# board.net
KiCad netlist of a schematic drawn in EAGLE
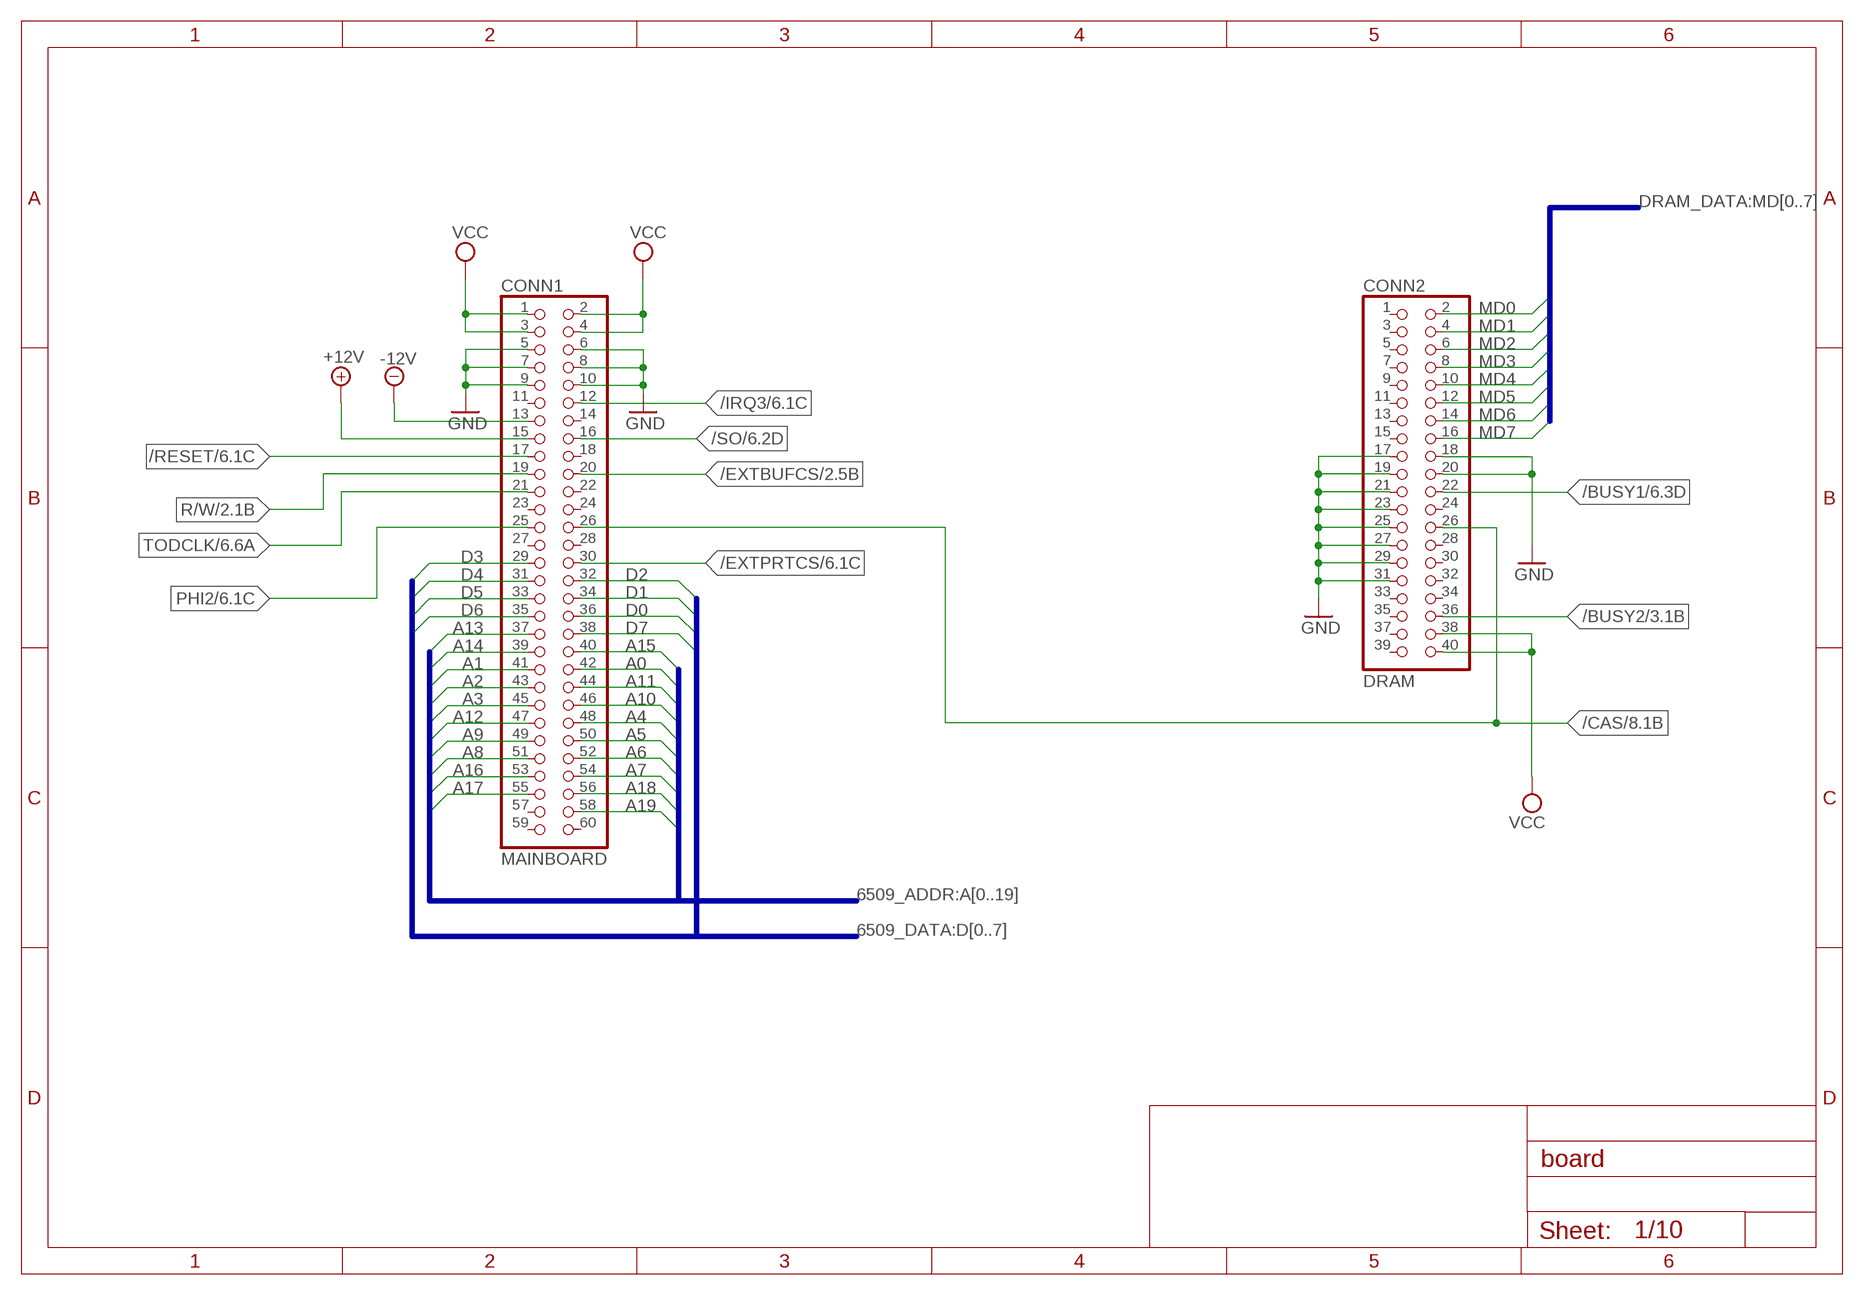
[diagram p0: schematic, sheet 1]
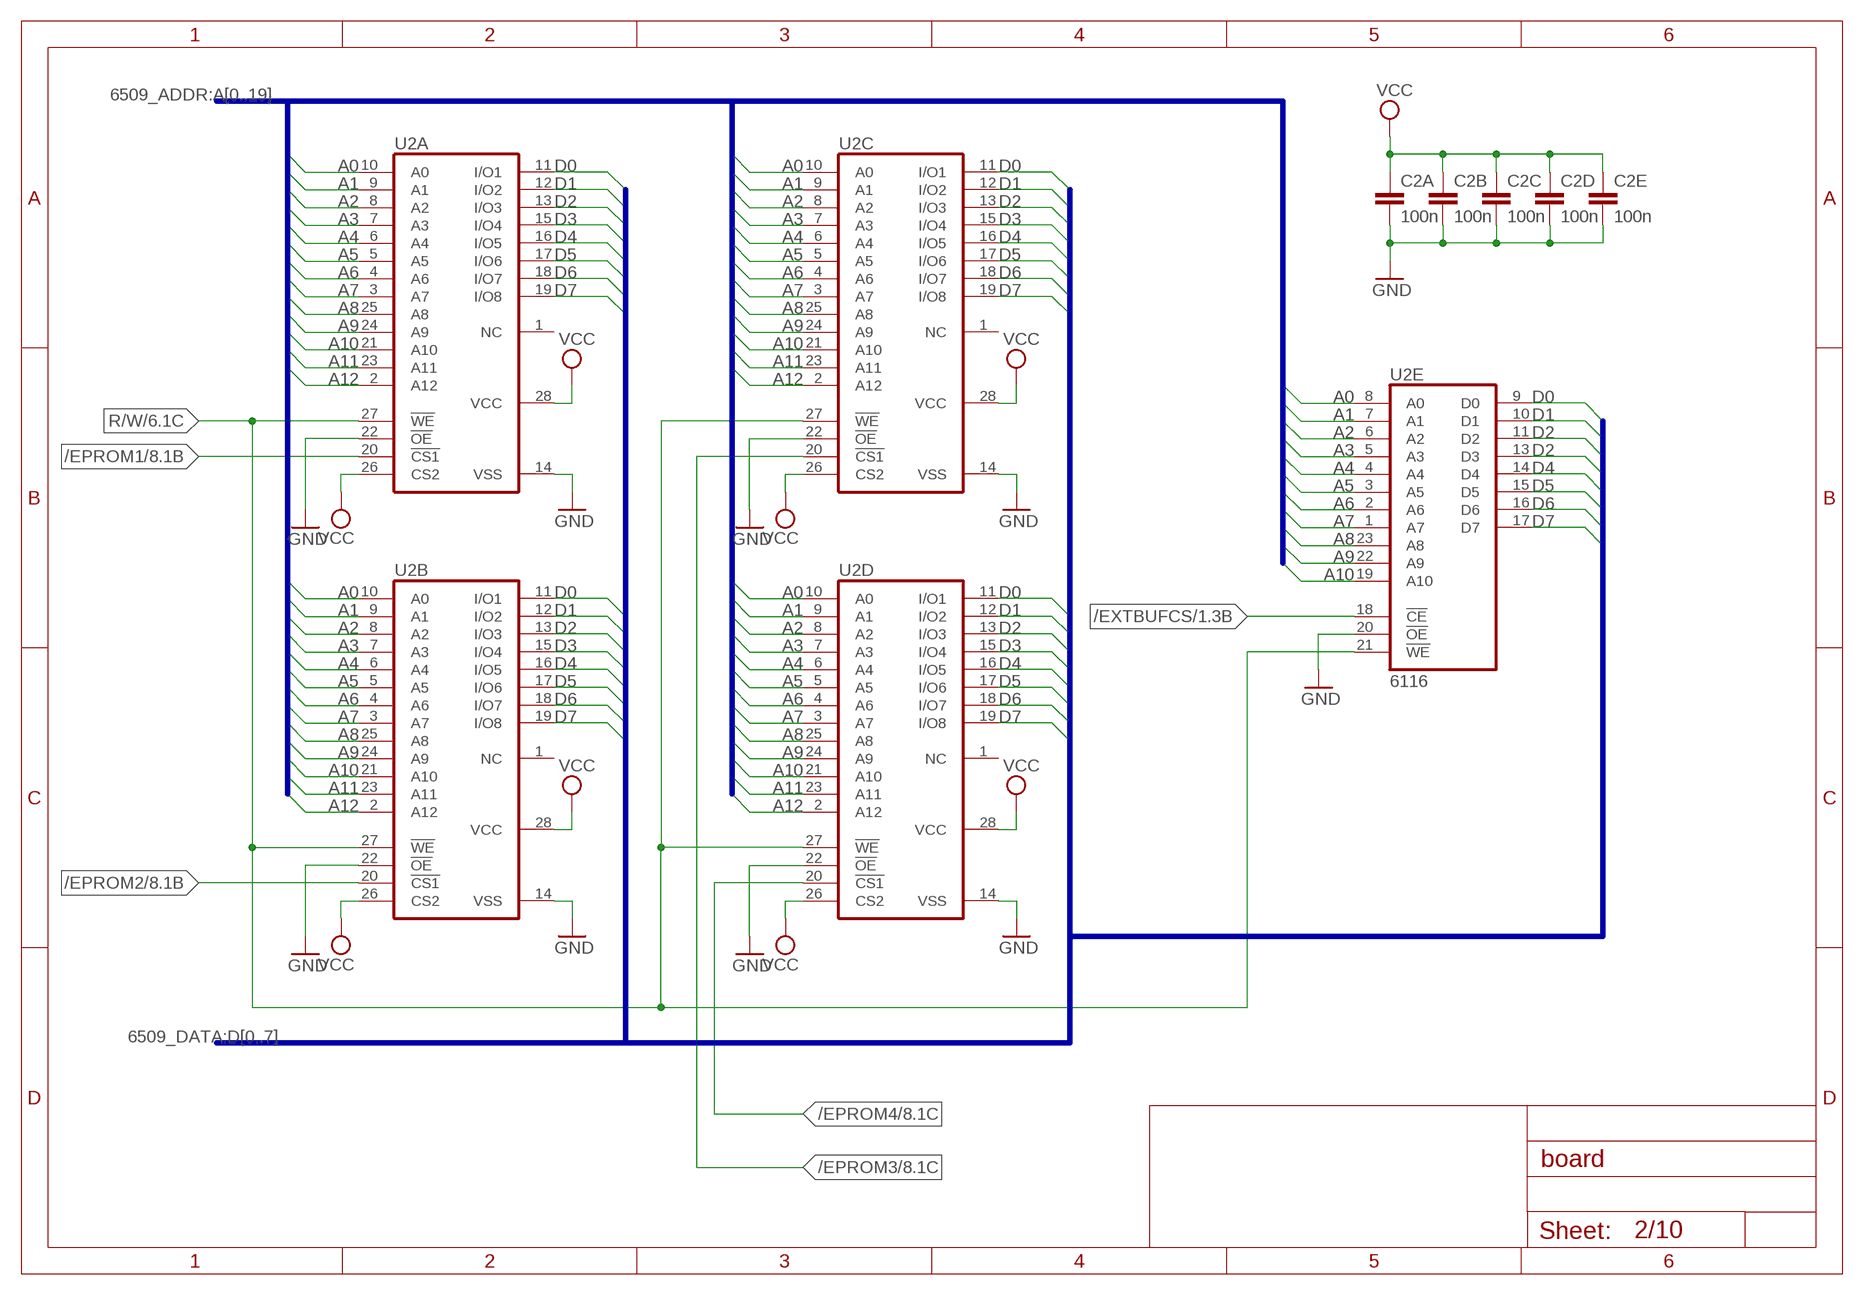
[diagram p1: schematic, sheet 2]
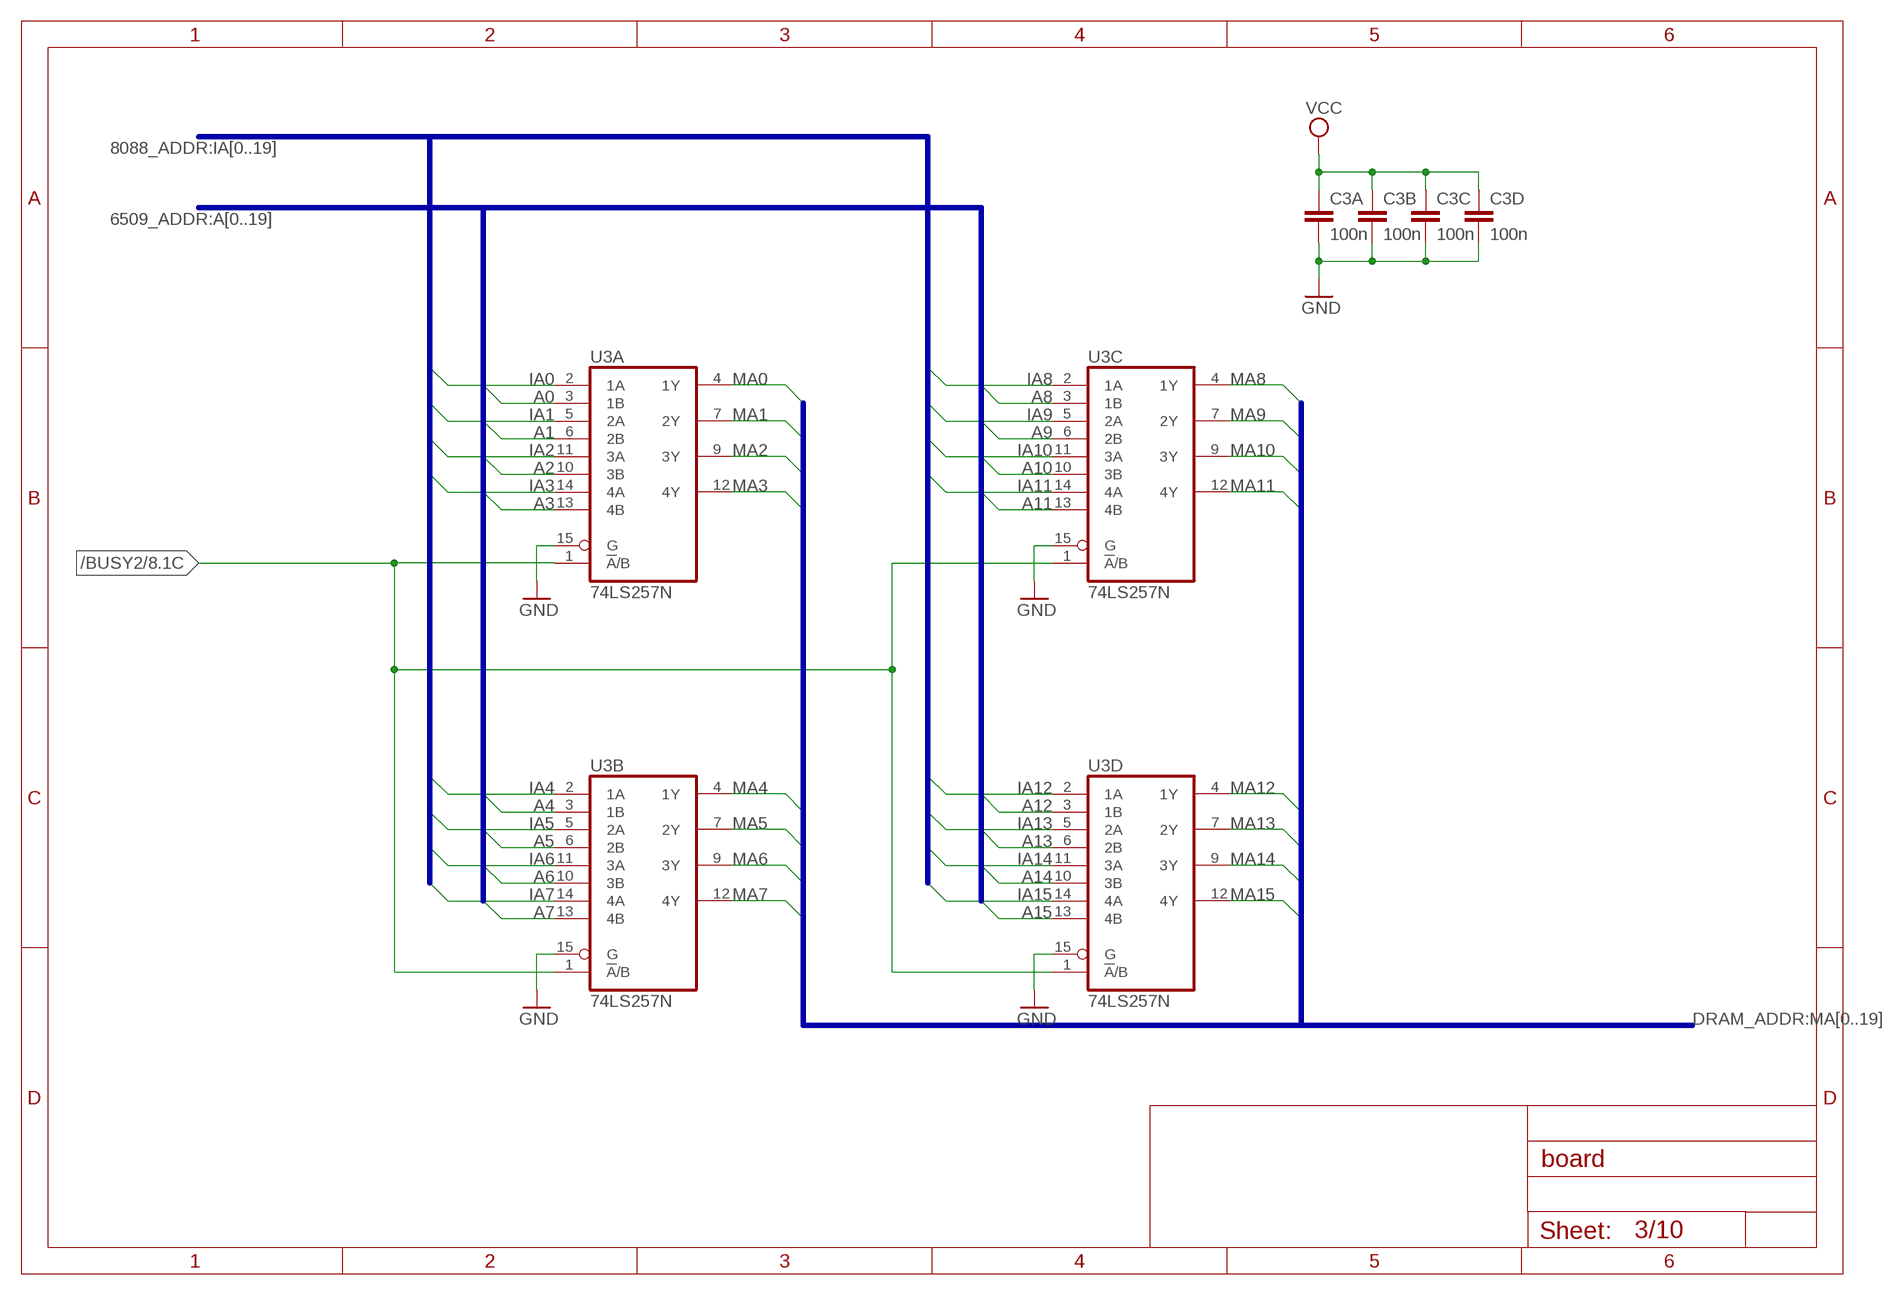
[diagram p2: schematic, sheet 3]
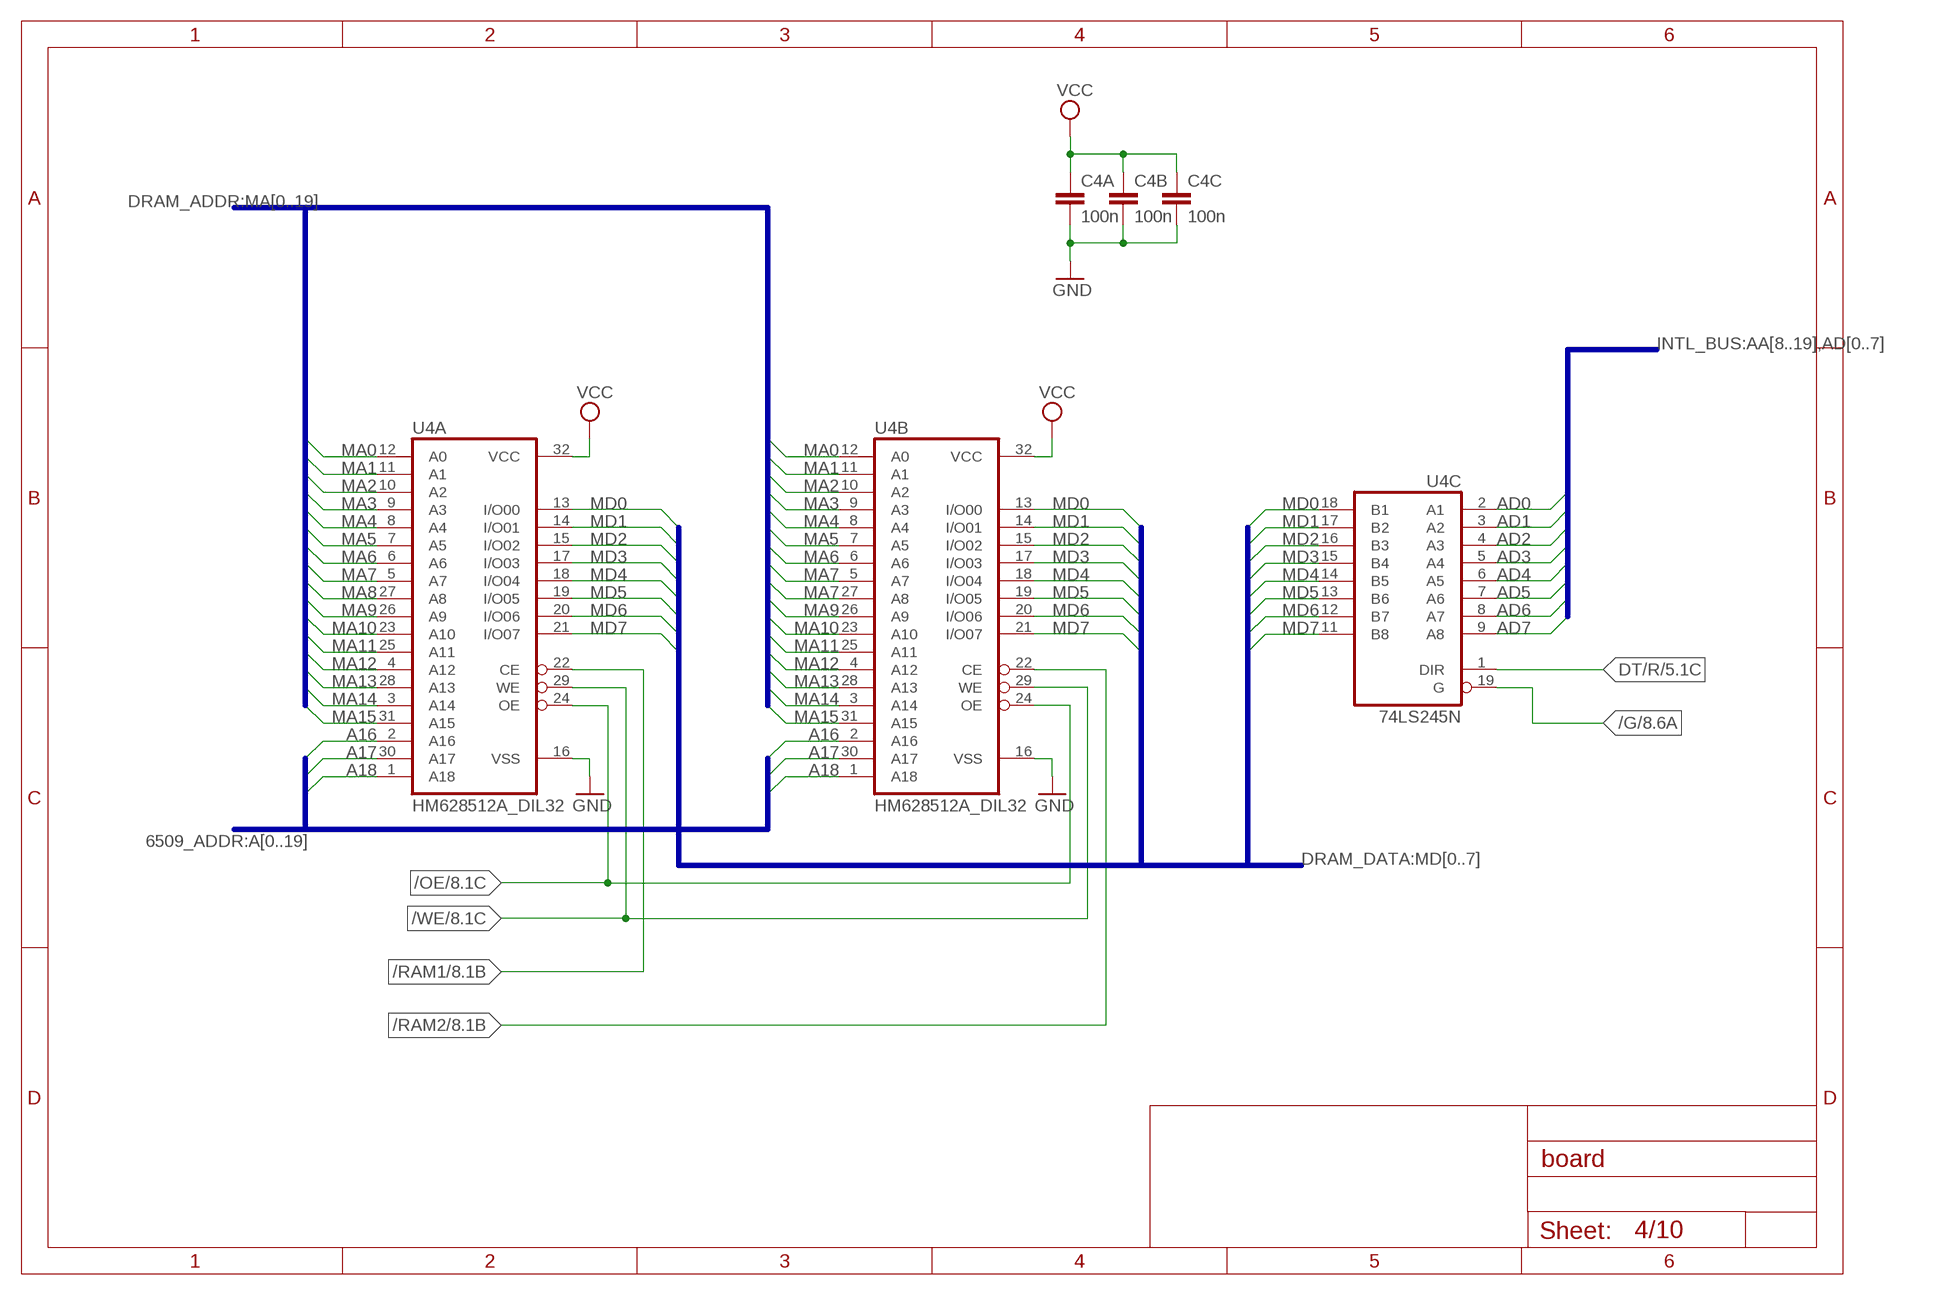
[diagram p3: schematic, sheet 4]
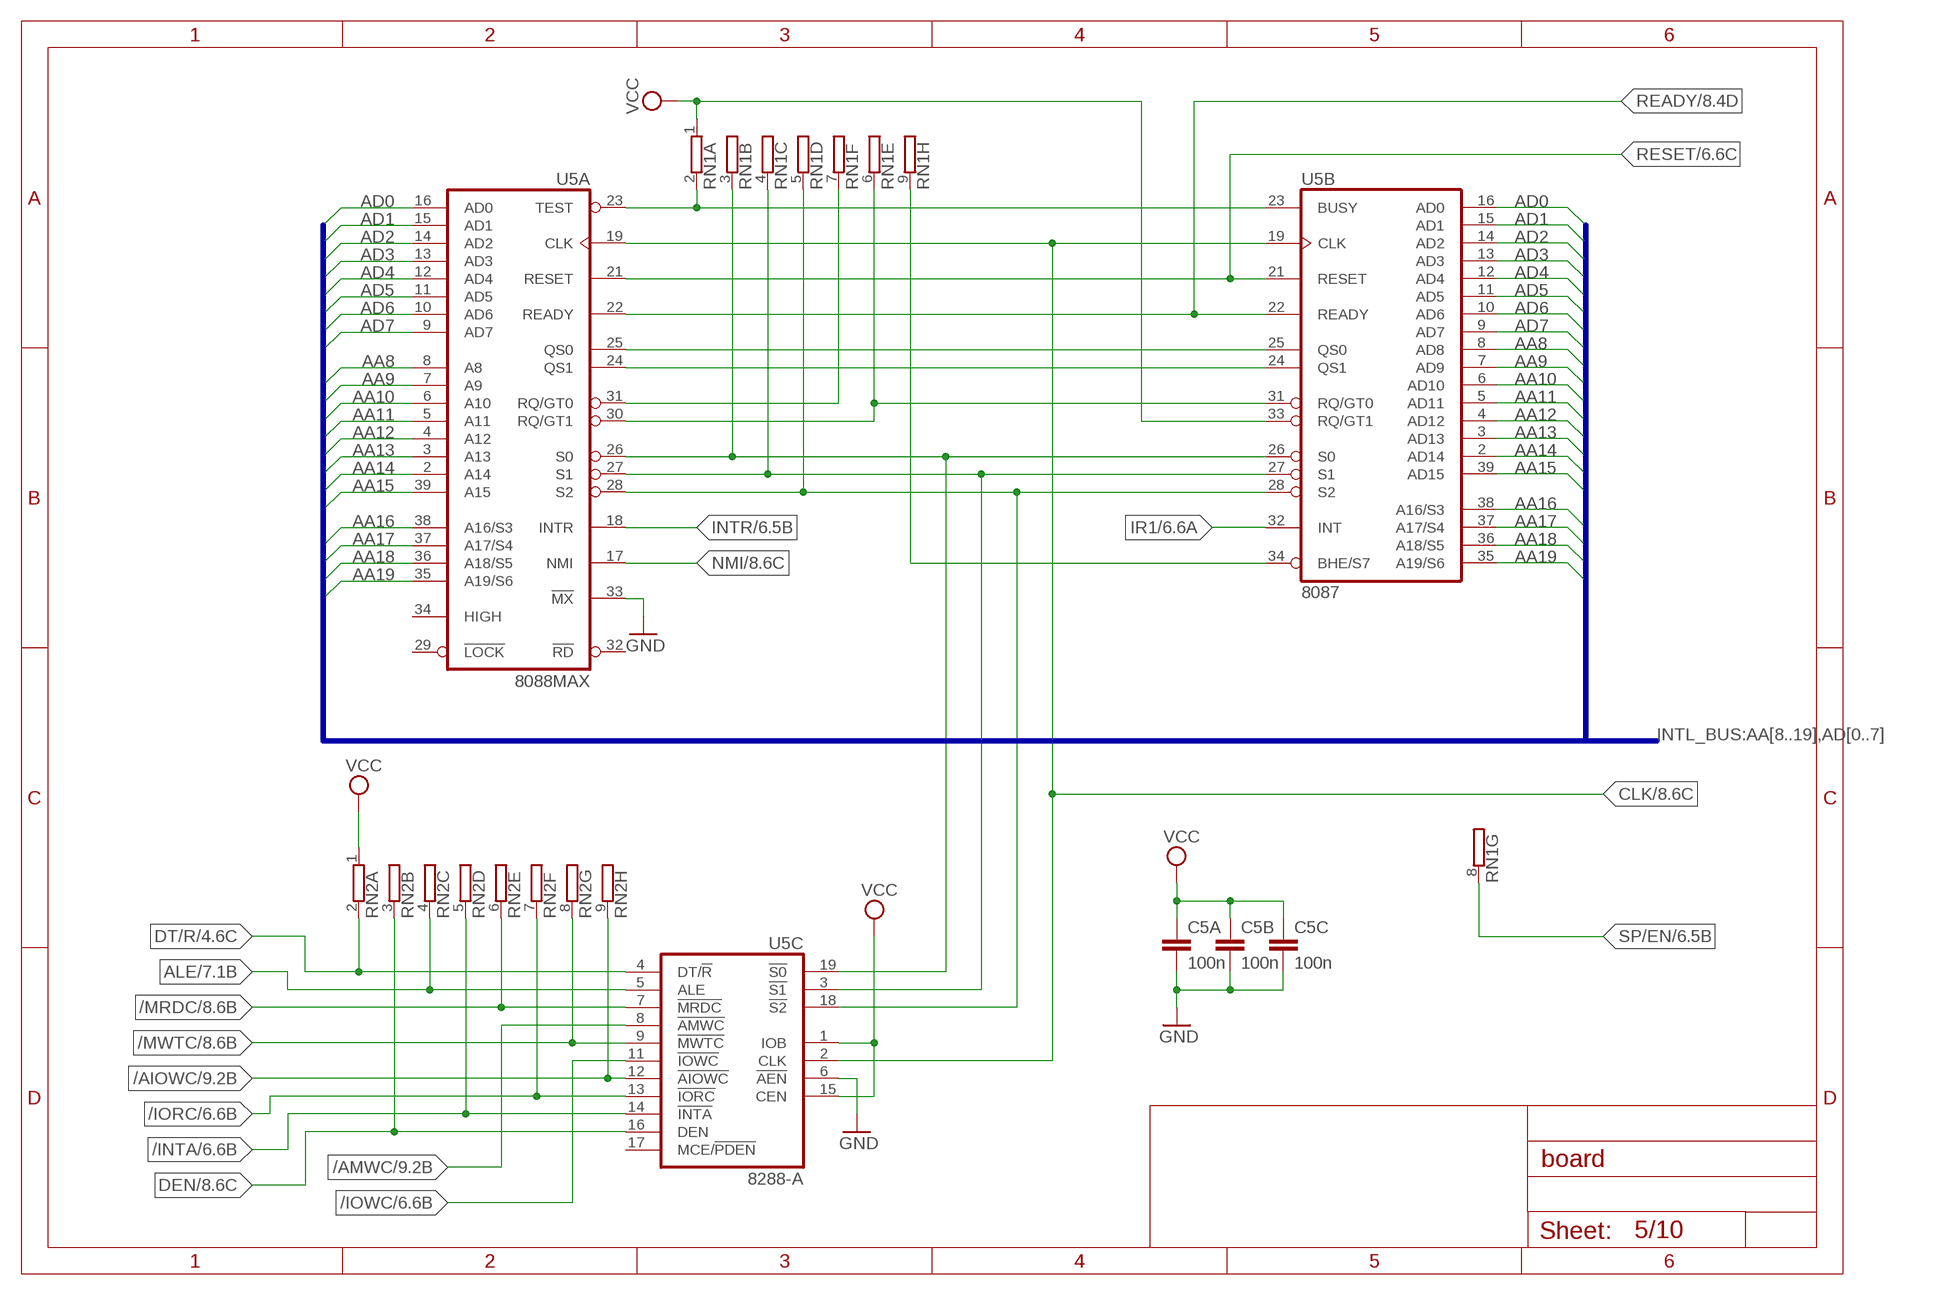
[diagram p4: schematic, sheet 5]
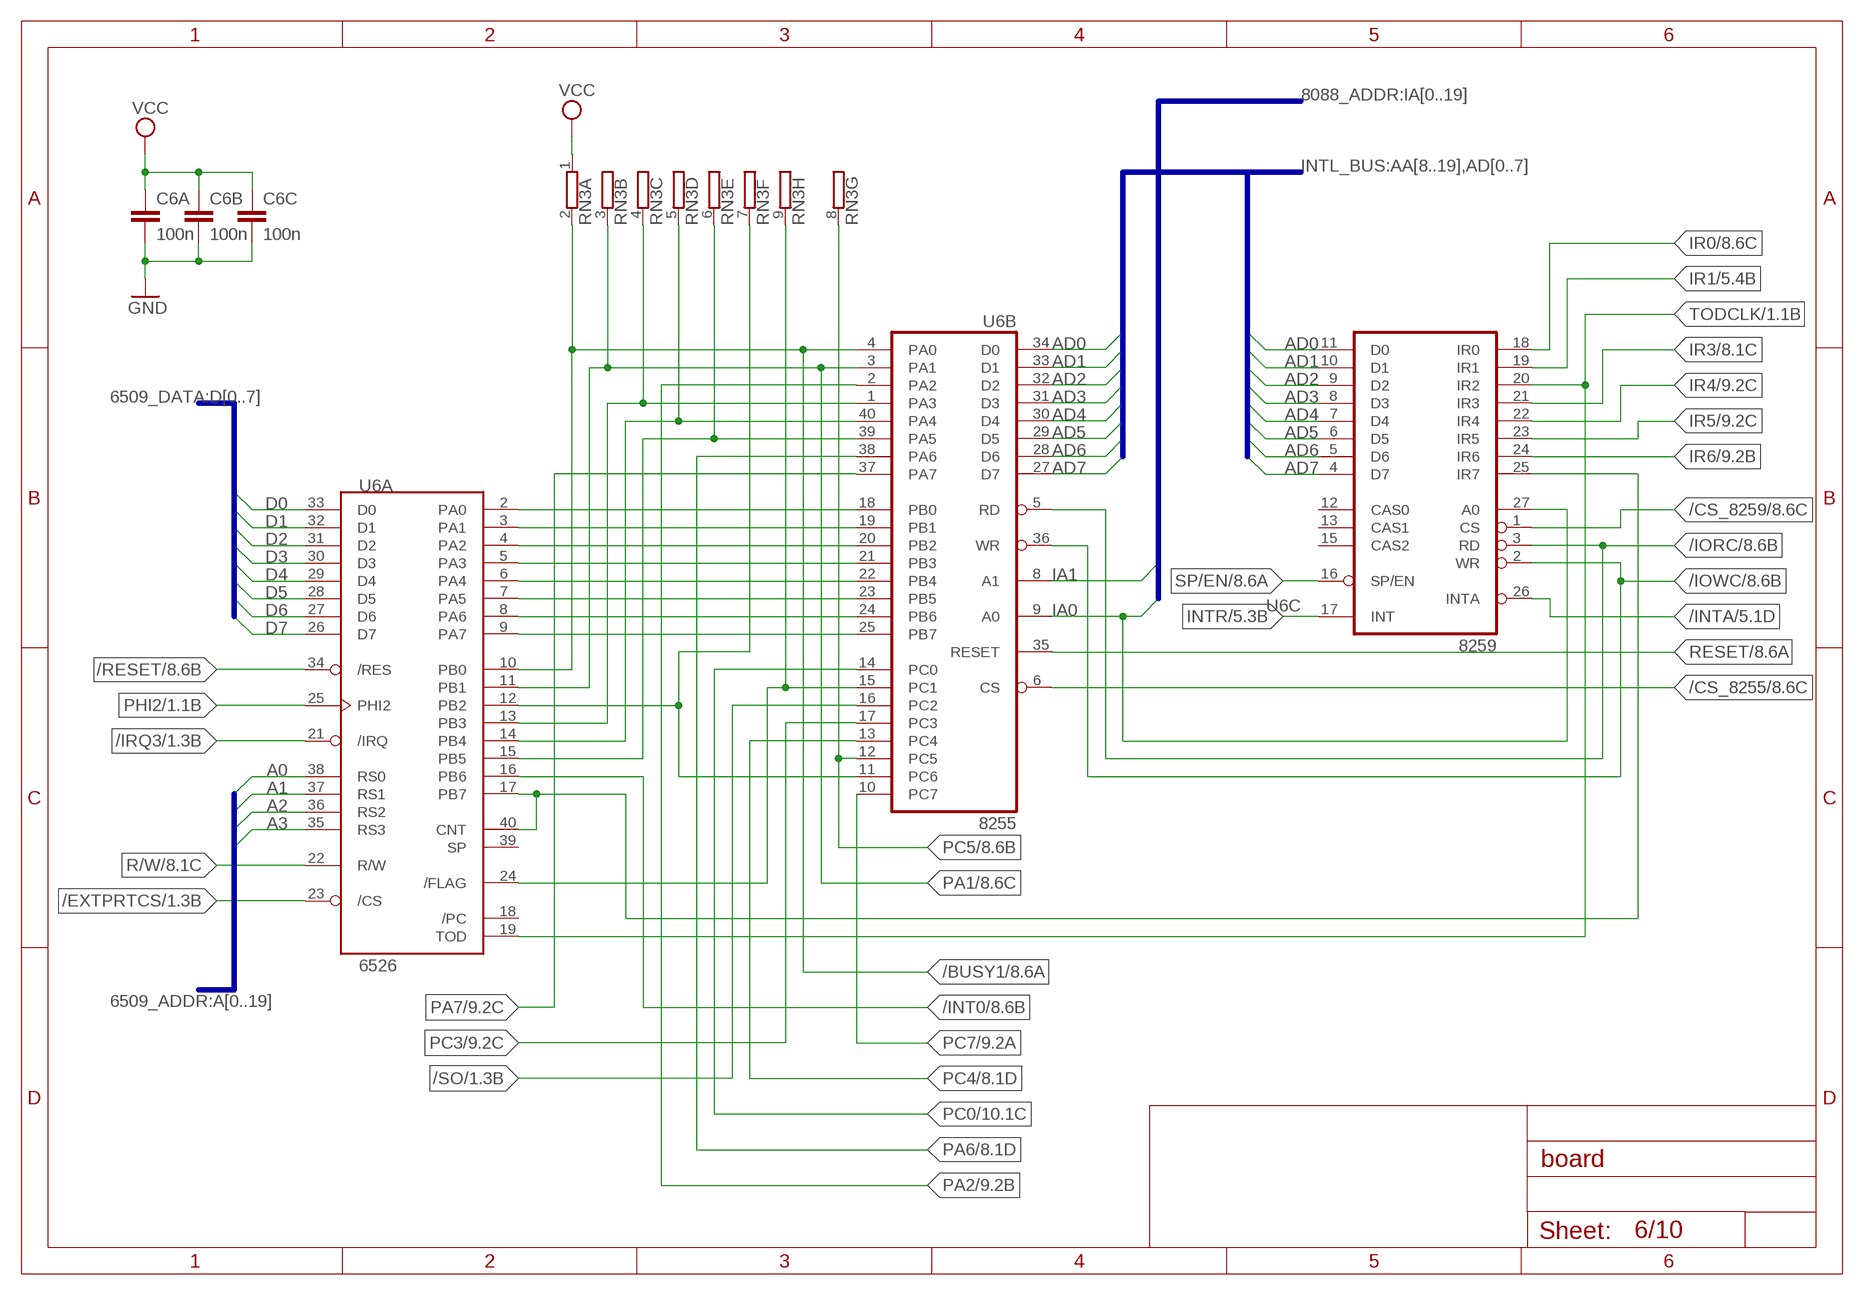
[diagram p5: schematic, sheet 6]
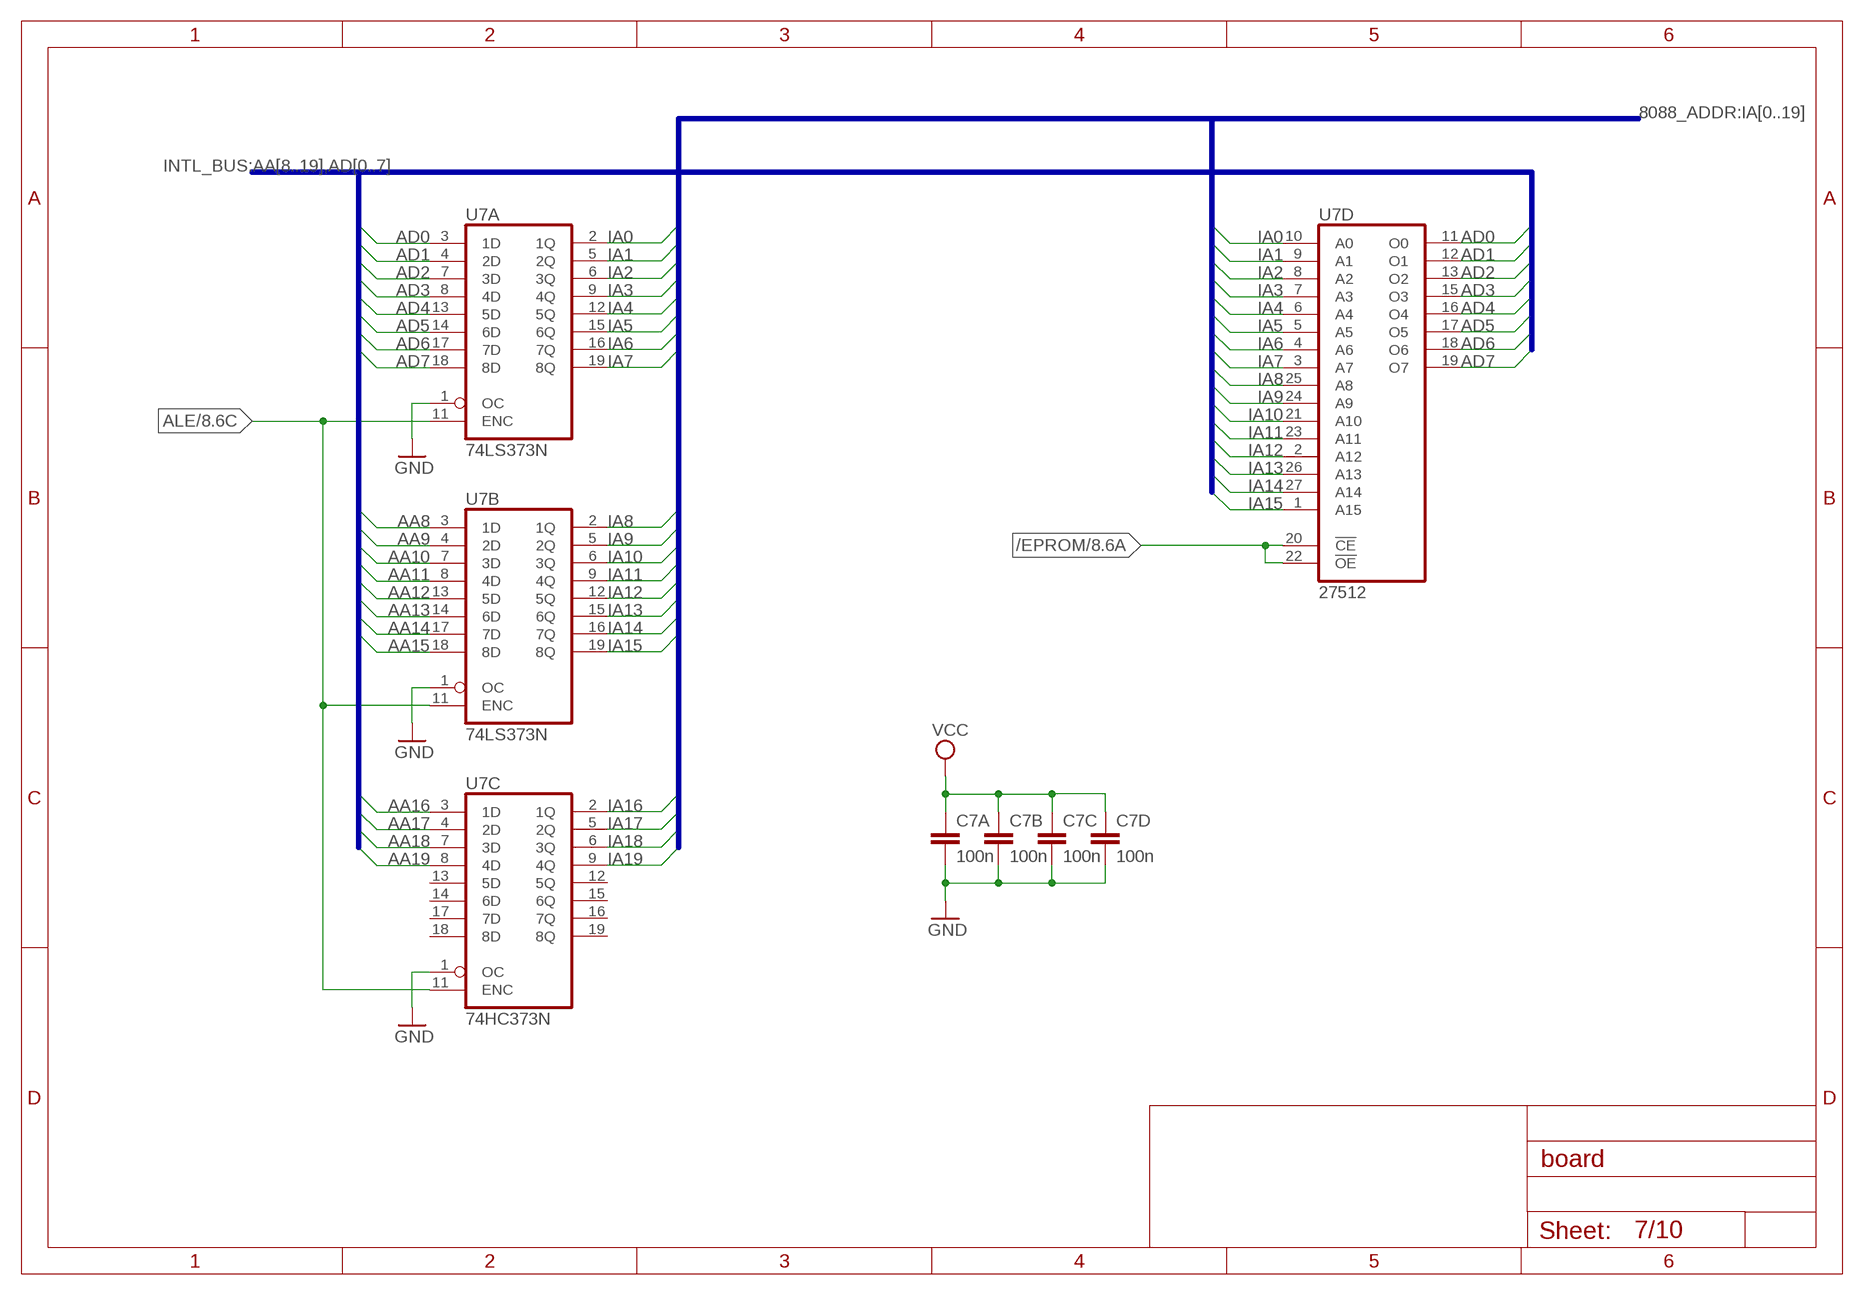
[diagram p6: schematic, sheet 7]
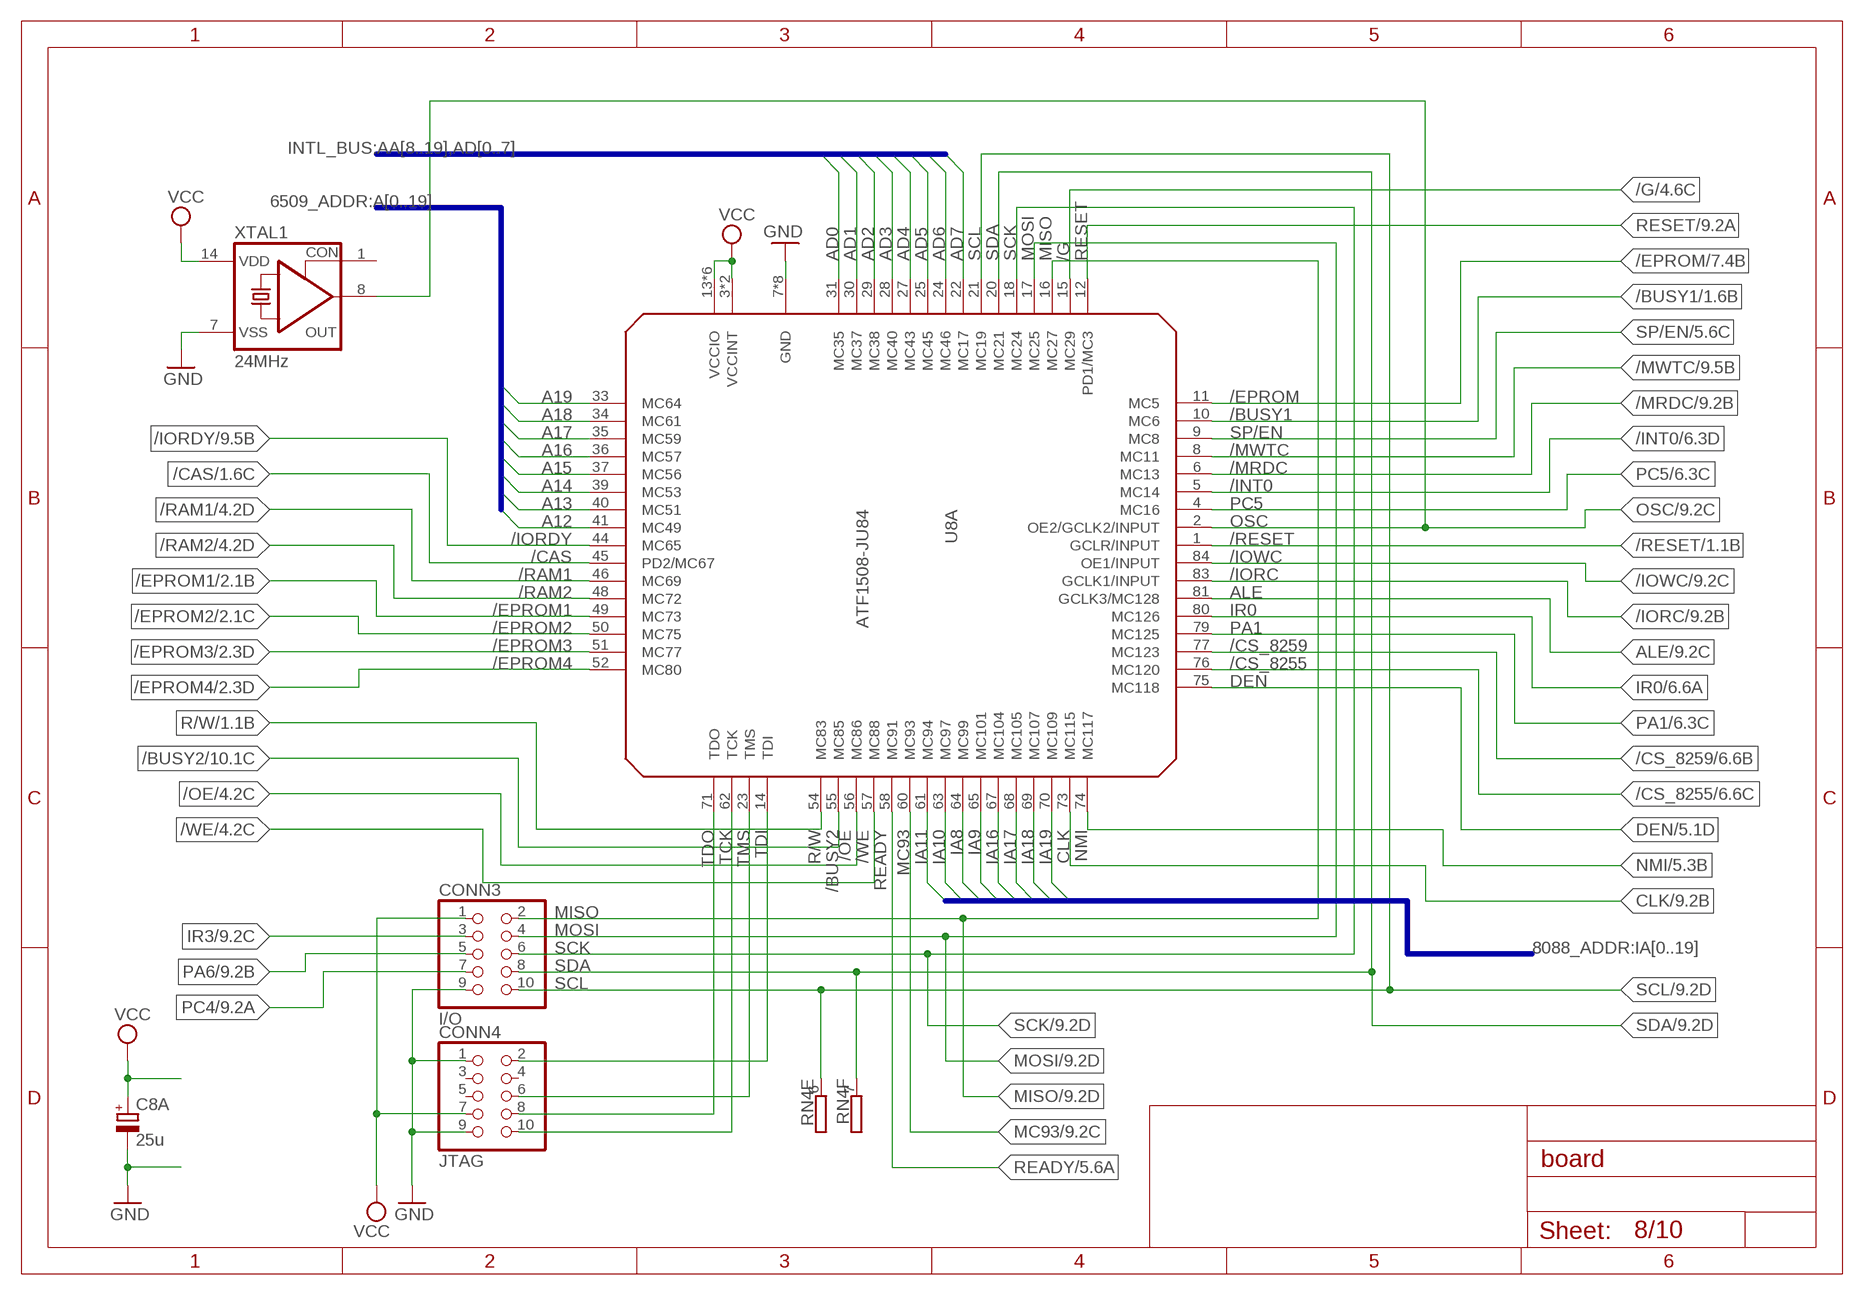
[diagram p7: schematic, sheet 8]
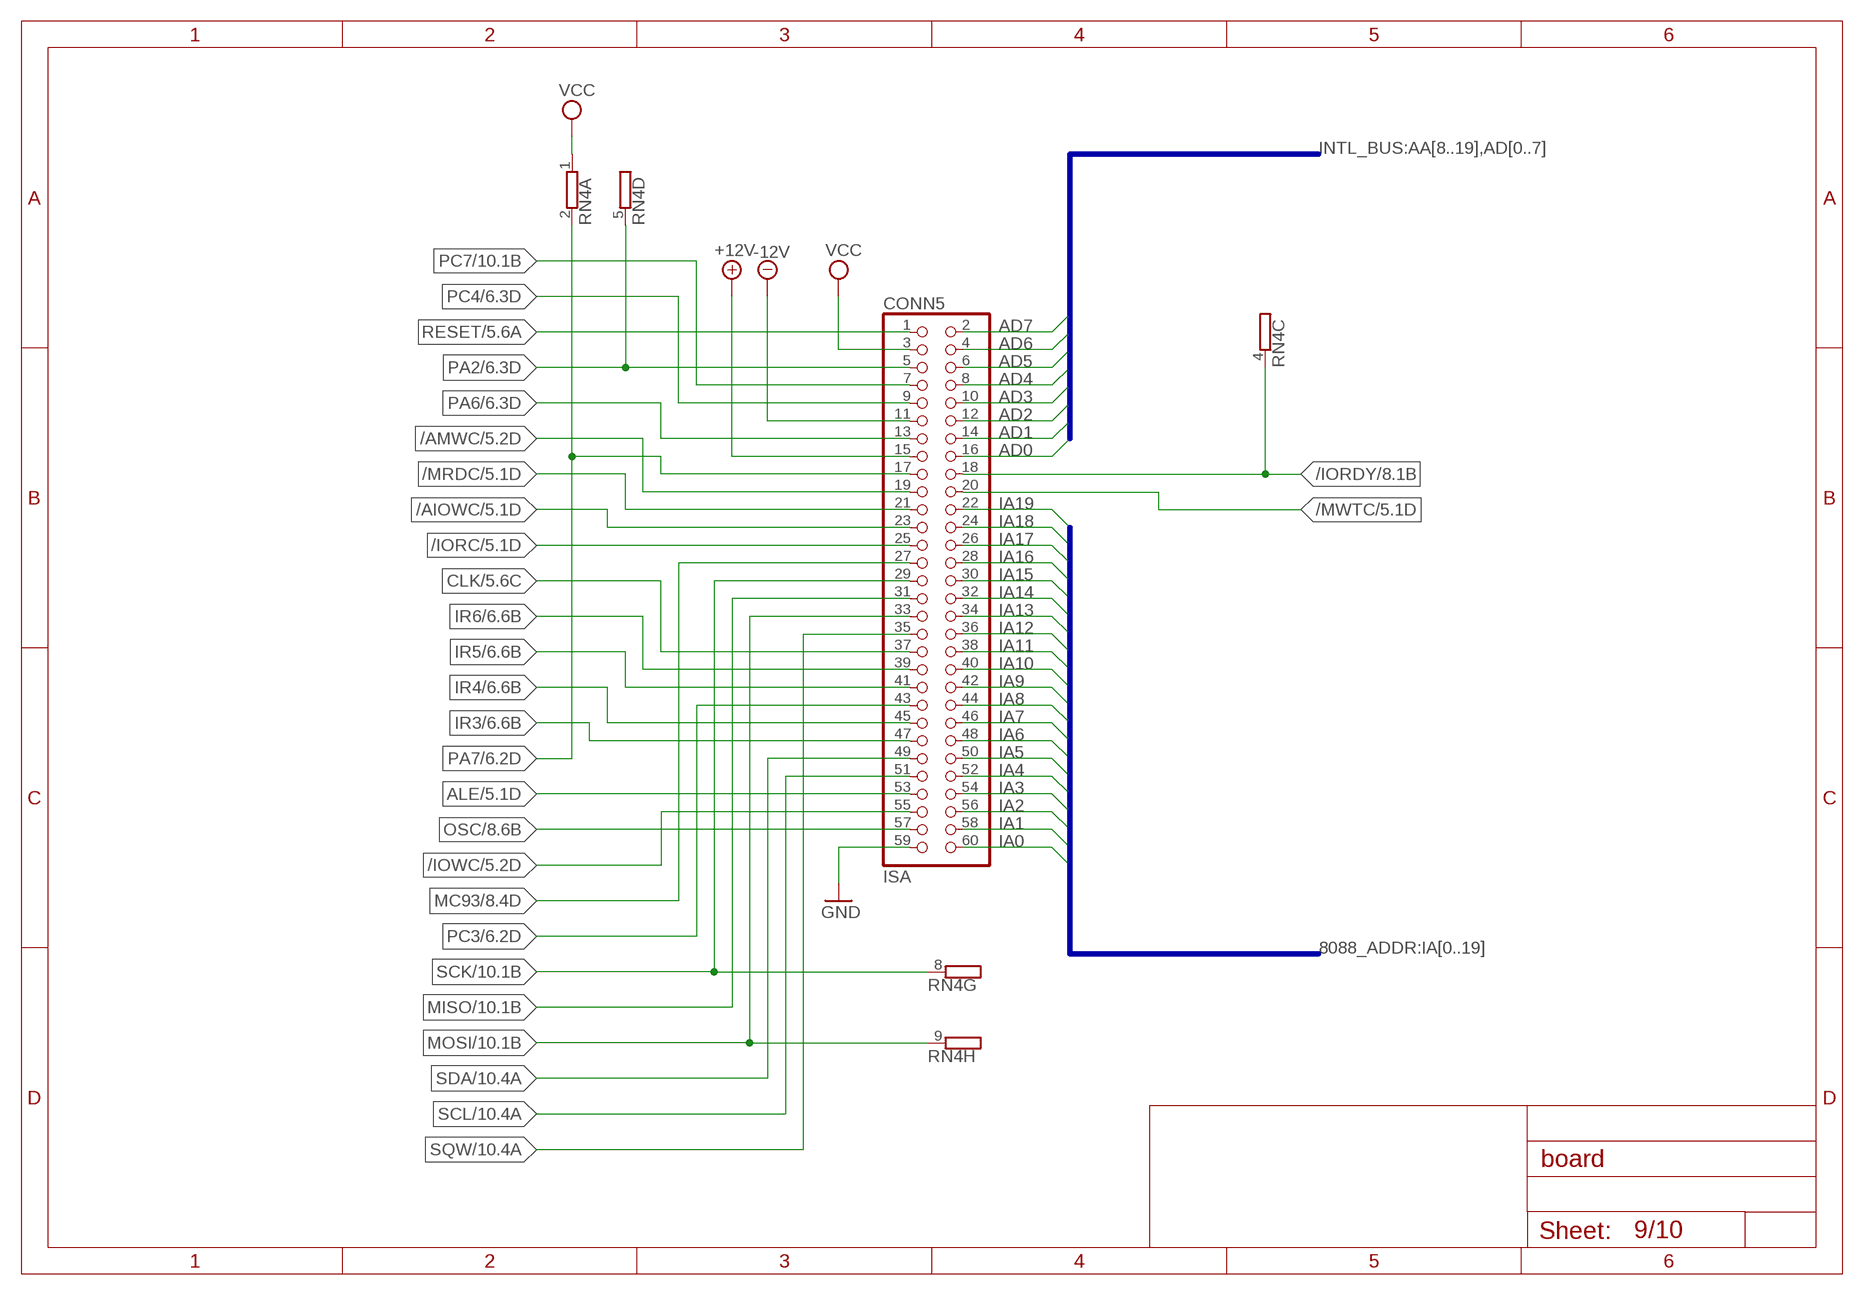
[diagram p8: schematic, sheet 9]
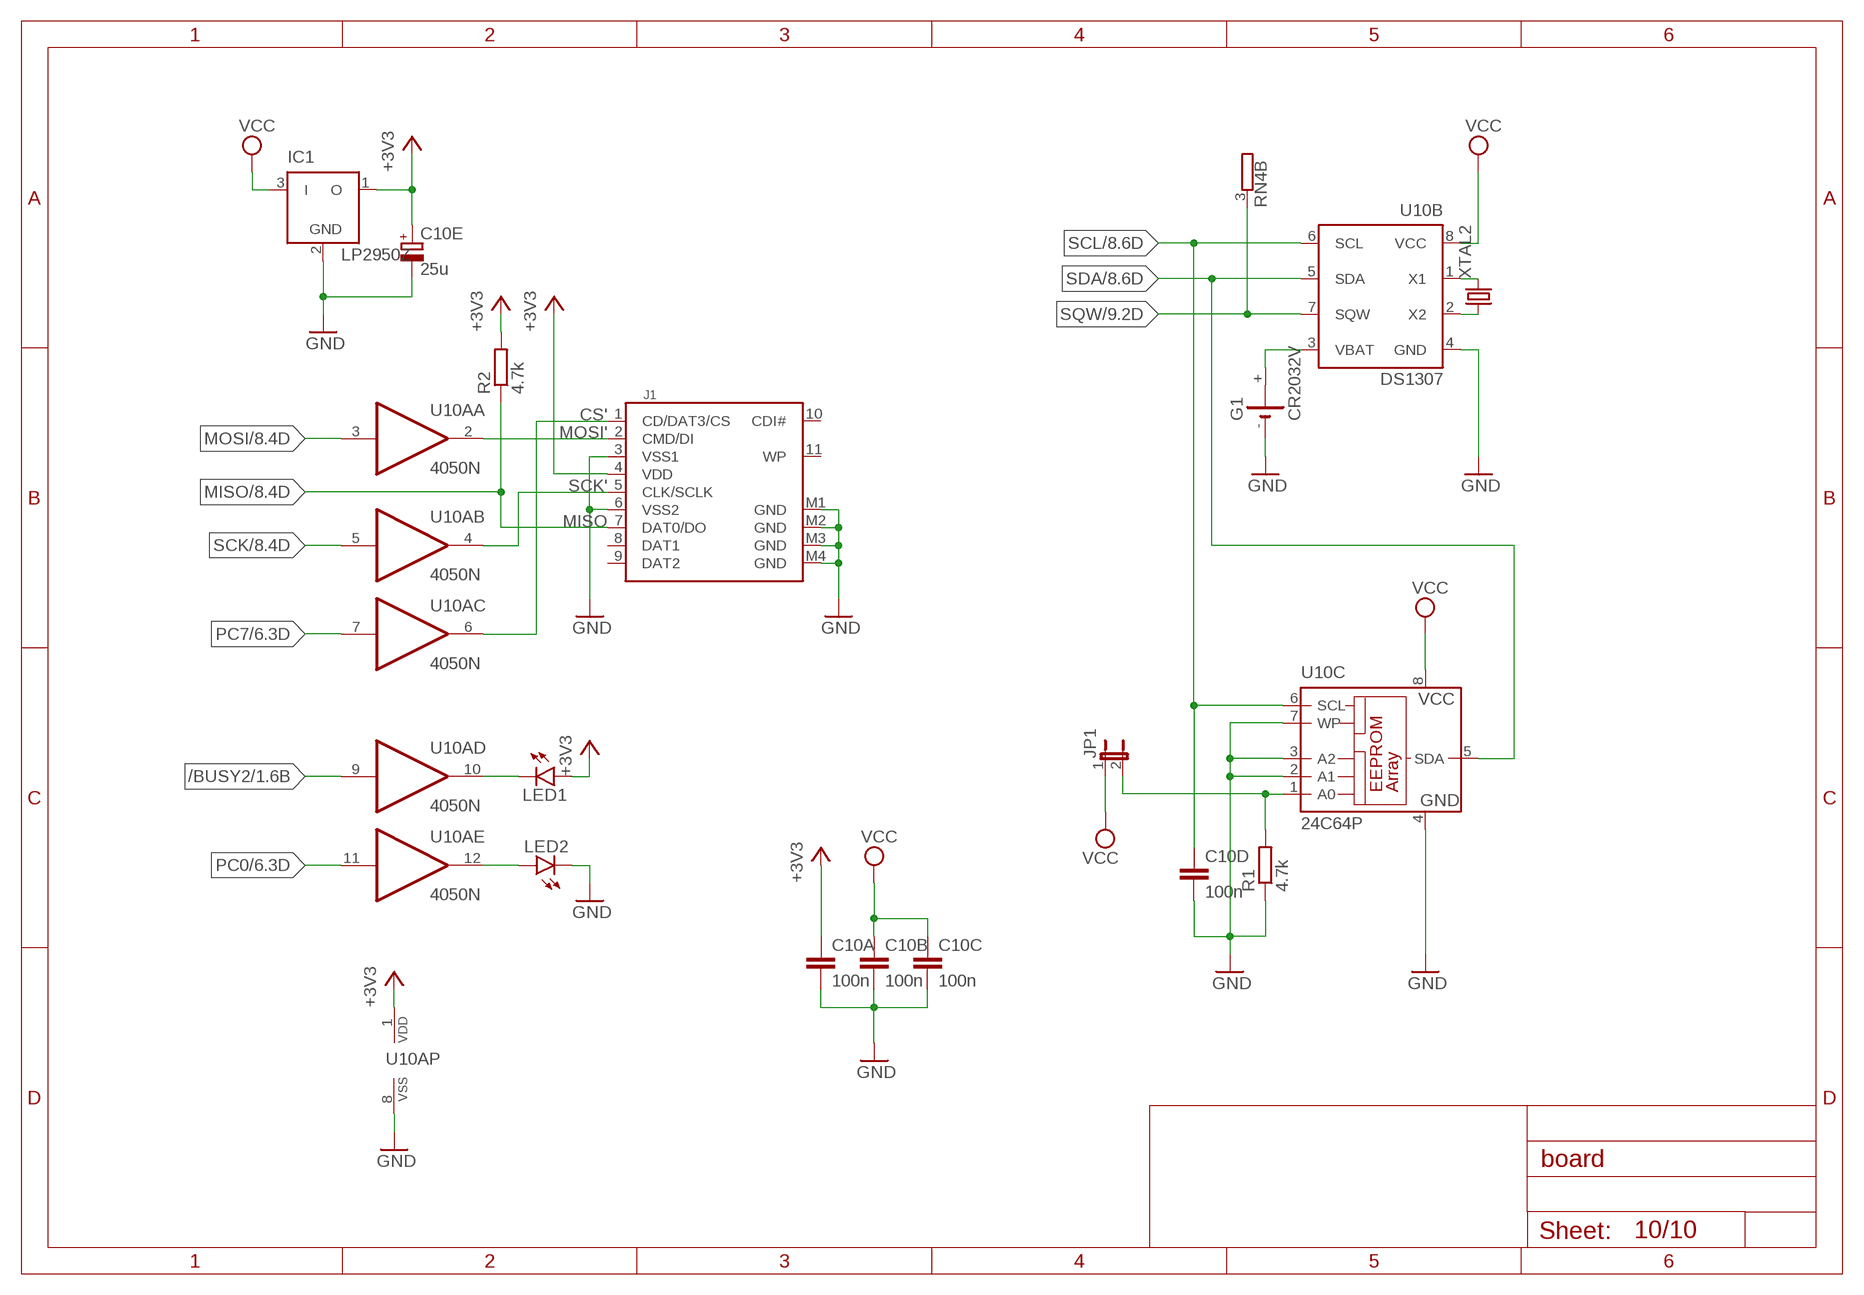
[diagram p9: schematic, sheet 10]

(export (version "E")
  (design (tool "Eeschema 10.0.6"))
  (components
    (comp (ref "C5A")
      (value "100n")
      (footprint "eagle-import:C050-025X075")
      (libsource (lib "eagle-import") (part "C-EU050-025X075"))
    )
    (comp (ref "C5B")
      (value "100n")
      (footprint "eagle-import:C050-025X075")
      (libsource (lib "eagle-import") (part "C-EU050-025X075"))
    )
    (comp (ref "C5C")
      (value "100n")
      (footprint "eagle-import:C050-025X075")
      (libsource (lib "eagle-import") (part "C-EU050-025X075"))
    )
    (comp (ref "RN1")
      (value "GE08R")
      (footprint "eagle-import:SIL9")
      (libsource (lib "eagle-import") (part "GE08R"))
    )
    (comp (ref "RN2")
      (value "GE08R")
      (footprint "eagle-import:SIL9")
      (libsource (lib "eagle-import") (part "GE08R"))
    )
    (comp (ref "U5A")
      (value "8088MAX")
      (footprint "eagle-import:DIL40")
      (libsource (lib "eagle-import") (part "8088MAX"))
    )
    (comp (ref "U5B")
      (value "8087")
      (footprint "eagle-import:DIL40")
      (libsource (lib "eagle-import") (part "8087"))
    )
    (comp (ref "U5C")
      (value "8288-A")
      (footprint "eagle-import:DIL20")
      (libsource (lib "eagle-import") (part "8288-A"))
    )
    (comp (ref "C8A")
      (value "25u")
      (footprint "eagle-import:E5-6")
      (libsource (lib "eagle-import") (part "CPOL-EUE5-6"))
    )
    (comp (ref "CONN3")
      (value "I/O")
      (footprint "eagle-import:2X05")
      (libsource (lib "eagle-import") (part "PINHD-2X5"))
    )
    (comp (ref "CONN4")
      (value "JTAG")
      (footprint "eagle-import:2X05")
      (libsource (lib "eagle-import") (part "PINHD-2X5"))
    )
    (comp (ref "RN4")
      (value "GE08R")
      (footprint "eagle-import:SIL9")
      (libsource (lib "eagle-import") (part "GE08R"))
    )
    (comp (ref "U8A")
      (value "ATF1508-JU84")
      (footprint "eagle-import:S84")
      (libsource (lib "eagle-import") (part "ATF1508-JU84"))
    )
    (comp (ref "XTAL1")
      (value "24MHz")
      (footprint "eagle-import:SG51")
      (libsource (lib "eagle-import") (part "CRYSTAL_RES-SG51"))
    )
    (comp (ref "C4A")
      (value "100n")
      (footprint "eagle-import:C050-025X075")
      (libsource (lib "eagle-import") (part "C-EU050-025X075"))
    )
    (comp (ref "C4B")
      (value "100n")
      (footprint "eagle-import:C050-025X075")
      (libsource (lib "eagle-import") (part "C-EU050-025X075"))
    )
    (comp (ref "C4C")
      (value "100n")
      (footprint "eagle-import:C050-025X075")
      (libsource (lib "eagle-import") (part "C-EU050-025X075"))
    )
    (comp (ref "U4A")
      (value "HM628512A_DIL32")
      (footprint "eagle-import:DIL32")
      (libsource (lib "eagle-import") (part "HM628512A_DIL32"))
    )
    (comp (ref "U4B")
      (value "HM628512A_DIL32")
      (footprint "eagle-import:DIL32")
      (libsource (lib "eagle-import") (part "HM628512A_DIL32"))
    )
    (comp (ref "U4C")
      (value "74LS245N")
      (footprint "eagle-import:DIL20")
      (libsource (lib "eagle-import") (part "74245NLS"))
    )
    (comp (ref "C10A")
      (value "100n")
      (footprint "eagle-import:C050-025X075")
      (libsource (lib "eagle-import") (part "C-EU050-025X075"))
    )
    (comp (ref "C10B")
      (value "100n")
      (footprint "eagle-import:C050-025X075")
      (libsource (lib "eagle-import") (part "C-EU050-025X075"))
    )
    (comp (ref "C10C")
      (value "100n")
      (footprint "eagle-import:C050-025X075")
      (libsource (lib "eagle-import") (part "C-EU050-025X075"))
    )
    (comp (ref "C10D")
      (value "100n")
      (footprint "eagle-import:C050-025X075")
      (libsource (lib "eagle-import") (part "C-EU050-025X075"))
    )
    (comp (ref "C10E")
      (value "25u")
      (footprint "eagle-import:E5-6")
      (libsource (lib "eagle-import") (part "CPOL-EUE5-6"))
    )
    (comp (ref "G1")
      (value "CR2032V")
      (footprint "eagle-import:CR2032V")
      (libsource (lib "eagle-import") (part "CR2032V"))
    )
    (comp (ref "IC1")
      (value "LP2950Z")
      (footprint "eagle-import:TO92")
      (libsource (lib "eagle-import") (part "LP2950Z"))
    )
    (comp (ref "J1")
      (value "SDCARD")
      (footprint "eagle-import:SDCMF-10915W010")
      (libsource (lib "eagle-import") (part "SDCARD"))
    )
    (comp (ref "JP1")
      (value "JP1E")
      (footprint "eagle-import:JP1")
      (libsource (lib "eagle-import") (part "JP1E"))
    )
    (comp (ref "LED1")
      (value "LEDSQR5.7X3.2")
      (footprint "eagle-import:U57X32")
      (libsource (lib "eagle-import") (part "LEDSQR5.7X3.2"))
    )
    (comp (ref "LED2")
      (value "LEDSQR5.7X3.2")
      (footprint "eagle-import:U57X32")
      (libsource (lib "eagle-import") (part "LEDSQR5.7X3.2"))
    )
    (comp (ref "R1")
      (value "4.7k")
      (footprint "eagle-import:0207_10")
      (libsource (lib "eagle-import") (part "R-EU_0207/10"))
    )
    (comp (ref "R2")
      (value "4.7k")
      (footprint "eagle-import:0207_10")
      (libsource (lib "eagle-import") (part "R-EU_0207/10"))
    )
    (comp (ref "U10A")
      (value "4050N")
      (footprint "eagle-import:DIL16")
      (libsource (lib "eagle-import") (part "4050N"))
    )
    (comp (ref "U10B")
      (value "DS1307")
      (footprint "eagle-import:DIL08")
      (libsource (lib "eagle-import") (part "DS1307"))
    )
    (comp (ref "U10C")
      (value "24C64P")
      (footprint "eagle-import:DIL8")
      (fields (field (name "MF") "RAMTRON INTERNATIONAL CORP") (field (name "MPN") "FM24C64-P"))
      (libsource (lib "eagle-import") (part "24PC64"))
    )
    (comp (ref "XTAL2")
      (value "CRYSTALTC38H")
      (footprint "eagle-import:TC38H")
      (libsource (lib "eagle-import") (part "CRYSTALTC38H"))
    )
    (comp (ref "C2A")
      (value "100n")
      (footprint "eagle-import:C050-025X075")
      (libsource (lib "eagle-import") (part "C-EU050-025X075"))
    )
    (comp (ref "C2B")
      (value "100n")
      (footprint "eagle-import:C050-025X075")
      (libsource (lib "eagle-import") (part "C-EU050-025X075"))
    )
    (comp (ref "C2C")
      (value "100n")
      (footprint "eagle-import:C050-025X075")
      (libsource (lib "eagle-import") (part "C-EU050-025X075"))
    )
    (comp (ref "C2D")
      (value "100n")
      (footprint "eagle-import:C050-025X075")
      (libsource (lib "eagle-import") (part "C-EU050-025X075"))
    )
    (comp (ref "C2E")
      (value "100n")
      (footprint "eagle-import:C050-025X075")
      (libsource (lib "eagle-import") (part "C-EU050-025X075"))
    )
    (comp (ref "U2A")
      (value "6264A")
      (footprint "eagle-import:DIL28-6")
      (libsource (lib "eagle-import") (part "6264A"))
    )
    (comp (ref "U2B")
      (value "6264A")
      (footprint "eagle-import:DIL28-6")
      (libsource (lib "eagle-import") (part "6264A"))
    )
    (comp (ref "U2C")
      (value "6264A")
      (footprint "eagle-import:DIL28-6")
      (libsource (lib "eagle-import") (part "6264A"))
    )
    (comp (ref "U2D")
      (value "6264A")
      (footprint "eagle-import:DIL28-6")
      (libsource (lib "eagle-import") (part "6264A"))
    )
    (comp (ref "U2E")
      (value "6116")
      (footprint "eagle-import:DIL24")
      (libsource (lib "eagle-import") (part "6116"))
    )
    (comp (ref "CONN5")
      (value "ISA")
      (footprint "eagle-import:2X30")
      (libsource (lib "eagle-import") (part "PINHD-2X30"))
    )
    (comp (ref "CONN1")
      (value "MAINBOARD")
      (footprint "eagle-import:2X30")
      (libsource (lib "eagle-import") (part "PINHD-2X30"))
    )
    (comp (ref "CONN2")
      (value "DRAM")
      (footprint "eagle-import:2X20")
      (libsource (lib "eagle-import") (part "PINHD-2X20"))
    )
    (comp (ref "C7A")
      (value "100n")
      (footprint "eagle-import:C050-025X075")
      (libsource (lib "eagle-import") (part "C-EU050-025X075"))
    )
    (comp (ref "C7B")
      (value "100n")
      (footprint "eagle-import:C050-025X075")
      (libsource (lib "eagle-import") (part "C-EU050-025X075"))
    )
    (comp (ref "C7C")
      (value "100n")
      (footprint "eagle-import:C050-025X075")
      (libsource (lib "eagle-import") (part "C-EU050-025X075"))
    )
    (comp (ref "C7D")
      (value "100n")
      (footprint "eagle-import:C050-025X075")
      (libsource (lib "eagle-import") (part "C-EU050-025X075"))
    )
    (comp (ref "U7A")
      (value "74LS373N")
      (footprint "eagle-import:DIL20")
      (libsource (lib "eagle-import") (part "74373NLS"))
    )
    (comp (ref "U7B")
      (value "74LS373N")
      (footprint "eagle-import:DIL20")
      (libsource (lib "eagle-import") (part "74373NLS"))
    )
    (comp (ref "U7C")
      (value "74HC373N")
      (footprint "eagle-import:DIL20")
      (libsource (lib "eagle-import") (part "74373NHC"))
    )
    (comp (ref "U7D")
      (value "27512")
      (footprint "eagle-import:DIL28")
      (libsource (lib "eagle-import") (part "27512"))
    )
    (comp (ref "C3A")
      (value "100n")
      (footprint "eagle-import:C050-025X075")
      (libsource (lib "eagle-import") (part "C-EU050-025X075"))
    )
    (comp (ref "C3B")
      (value "100n")
      (footprint "eagle-import:C050-025X075")
      (libsource (lib "eagle-import") (part "C-EU050-025X075"))
    )
    (comp (ref "C3C")
      (value "100n")
      (footprint "eagle-import:C050-025X075")
      (libsource (lib "eagle-import") (part "C-EU050-025X075"))
    )
    (comp (ref "C3D")
      (value "100n")
      (footprint "eagle-import:C050-025X075")
      (libsource (lib "eagle-import") (part "C-EU050-025X075"))
    )
    (comp (ref "U3A")
      (value "74LS257N")
      (footprint "eagle-import:DIL16")
      (libsource (lib "eagle-import") (part "74257NLS"))
    )
    (comp (ref "U3B")
      (value "74LS257N")
      (footprint "eagle-import:DIL16")
      (libsource (lib "eagle-import") (part "74257NLS"))
    )
    (comp (ref "U3C")
      (value "74LS257N")
      (footprint "eagle-import:DIL16")
      (libsource (lib "eagle-import") (part "74257NLS"))
    )
    (comp (ref "U3D")
      (value "74LS257N")
      (footprint "eagle-import:DIL16")
      (libsource (lib "eagle-import") (part "74257NLS"))
    )
    (comp (ref "C6A")
      (value "100n")
      (footprint "eagle-import:C050-025X075")
      (libsource (lib "eagle-import") (part "C-EU050-025X075"))
    )
    (comp (ref "C6B")
      (value "100n")
      (footprint "eagle-import:C050-025X075")
      (libsource (lib "eagle-import") (part "C-EU050-025X075"))
    )
    (comp (ref "C6C")
      (value "100n")
      (footprint "eagle-import:C050-025X075")
      (libsource (lib "eagle-import") (part "C-EU050-025X075"))
    )
    (comp (ref "RN3")
      (value "GE08R")
      (footprint "eagle-import:SIL9")
      (libsource (lib "eagle-import") (part "GE08R"))
    )
    (comp (ref "U6A")
      (value "6526")
      (footprint "eagle-import:DIP40")
      (libsource (lib "eagle-import") (part "6526"))
    )
    (comp (ref "U6B")
      (value "8255")
      (footprint "eagle-import:DIL40")
      (libsource (lib "eagle-import") (part "8255A"))
    )
    (comp (ref "U6C")
      (value "8259")
      (footprint "eagle-import:DIL28-6")
      (libsource (lib "eagle-import") (part "8259A"))
    )
  )
  (nets
    (net (code "301") (name "+3V3") (class "Default")
      (node (ref "C10A") (pin "1") (pinfunction "1_1") (pintype "passive"))
      (node (ref "C10E") (pin "+") (pinfunction "+_+") (pintype "passive"))
      (node (ref "IC1") (pin "1") (pinfunction "O_1") (pintype "input"))
      (node (ref "J1") (pin "4") (pinfunction "VDD_4") (pintype "power_in"))
      (node (ref "LED1") (pin "A") (pinfunction "A_A") (pintype "passive"))
      (node (ref "R2") (pin "2") (pinfunction "2_2") (pintype "passive"))
      (node (ref "U10A") (pin "1") (pinfunction "VDD_1") (pintype "power_in"))
    )
    (net (code "302") (name "+12V") (class "Default")
      (node (ref "CONN1") (pin "15") (pinfunction "15_15") (pintype "passive"))
      (node (ref "CONN5") (pin "15") (pinfunction "15_15") (pintype "passive"))
    )
    (net (code "303") (name "-12V") (class "Default")
      (node (ref "CONN1") (pin "13") (pinfunction "13_13") (pintype "passive"))
      (node (ref "CONN5") (pin "11") (pinfunction "11_11") (pintype "passive"))
    )
    (net (code "328") (name "A0") (class "Default")
      (node (ref "CONN1") (pin "42") (pinfunction "42_42") (pintype "passive"))
      (node (ref "U2A") (pin "10") (pinfunction "A0_10") (pintype "input"))
      (node (ref "U2B") (pin "10") (pinfunction "A0_10") (pintype "input"))
      (node (ref "U2C") (pin "10") (pinfunction "A0_10") (pintype "input"))
      (node (ref "U2D") (pin "10") (pinfunction "A0_10") (pintype "input"))
      (node (ref "U2E") (pin "8") (pinfunction "A0_8") (pintype "input"))
      (node (ref "U3A") (pin "3") (pinfunction "1B_3") (pintype "input"))
      (node (ref "U6A") (pin "38") (pinfunction "RS0_38") (pintype "input"))
    )
    (net (code "329") (name "A1") (class "Default")
      (node (ref "CONN1") (pin "41") (pinfunction "41_41") (pintype "passive"))
      (node (ref "U2A") (pin "9") (pinfunction "A1_9") (pintype "input"))
      (node (ref "U2B") (pin "9") (pinfunction "A1_9") (pintype "input"))
      (node (ref "U2C") (pin "9") (pinfunction "A1_9") (pintype "input"))
      (node (ref "U2D") (pin "9") (pinfunction "A1_9") (pintype "input"))
      (node (ref "U2E") (pin "7") (pinfunction "A1_7") (pintype "input"))
      (node (ref "U3A") (pin "6") (pinfunction "2B_6") (pintype "input"))
      (node (ref "U6A") (pin "37") (pinfunction "RS1_37") (pintype "input"))
    )
    (net (code "330") (name "A2") (class "Default")
      (node (ref "CONN1") (pin "43") (pinfunction "43_43") (pintype "passive"))
      (node (ref "U2A") (pin "8") (pinfunction "A2_8") (pintype "input"))
      (node (ref "U2B") (pin "8") (pinfunction "A2_8") (pintype "input"))
      (node (ref "U2C") (pin "8") (pinfunction "A2_8") (pintype "input"))
      (node (ref "U2D") (pin "8") (pinfunction "A2_8") (pintype "input"))
      (node (ref "U2E") (pin "6") (pinfunction "A2_6") (pintype "input"))
      (node (ref "U3A") (pin "10") (pinfunction "3B_10") (pintype "input"))
      (node (ref "U6A") (pin "36") (pinfunction "RS2_36") (pintype "input"))
    )
    (net (code "331") (name "A3") (class "Default")
      (node (ref "CONN1") (pin "45") (pinfunction "45_45") (pintype "passive"))
      (node (ref "U2A") (pin "7") (pinfunction "A3_7") (pintype "input"))
      (node (ref "U2B") (pin "7") (pinfunction "A3_7") (pintype "input"))
      (node (ref "U2C") (pin "7") (pinfunction "A3_7") (pintype "input"))
      (node (ref "U2D") (pin "7") (pinfunction "A3_7") (pintype "input"))
      (node (ref "U2E") (pin "5") (pinfunction "A3_5") (pintype "input"))
      (node (ref "U3A") (pin "13") (pinfunction "4B_13") (pintype "input"))
      (node (ref "U6A") (pin "35") (pinfunction "RS3_35") (pintype "input"))
    )
    (net (code "332") (name "A4") (class "Default")
      (node (ref "CONN1") (pin "48") (pinfunction "48_48") (pintype "passive"))
      (node (ref "U2A") (pin "6") (pinfunction "A4_6") (pintype "input"))
      (node (ref "U2B") (pin "6") (pinfunction "A4_6") (pintype "input"))
      (node (ref "U2C") (pin "6") (pinfunction "A4_6") (pintype "input"))
      (node (ref "U2D") (pin "6") (pinfunction "A4_6") (pintype "input"))
      (node (ref "U2E") (pin "4") (pinfunction "A4_4") (pintype "input"))
      (node (ref "U3B") (pin "3") (pinfunction "1B_3") (pintype "input"))
    )
    (net (code "333") (name "A5") (class "Default")
      (node (ref "CONN1") (pin "50") (pinfunction "50_50") (pintype "passive"))
      (node (ref "U2A") (pin "5") (pinfunction "A5_5") (pintype "input"))
      (node (ref "U2B") (pin "5") (pinfunction "A5_5") (pintype "input"))
      (node (ref "U2C") (pin "5") (pinfunction "A5_5") (pintype "input"))
      (node (ref "U2D") (pin "5") (pinfunction "A5_5") (pintype "input"))
      (node (ref "U2E") (pin "3") (pinfunction "A5_3") (pintype "input"))
      (node (ref "U3B") (pin "6") (pinfunction "2B_6") (pintype "input"))
    )
    (net (code "334") (name "A6") (class "Default")
      (node (ref "CONN1") (pin "52") (pinfunction "52_52") (pintype "passive"))
      (node (ref "U2A") (pin "4") (pinfunction "A6_4") (pintype "input"))
      (node (ref "U2B") (pin "4") (pinfunction "A6_4") (pintype "input"))
      (node (ref "U2C") (pin "4") (pinfunction "A6_4") (pintype "input"))
      (node (ref "U2D") (pin "4") (pinfunction "A6_4") (pintype "input"))
      (node (ref "U2E") (pin "2") (pinfunction "A6_2") (pintype "input"))
      (node (ref "U3B") (pin "10") (pinfunction "3B_10") (pintype "input"))
    )
    (net (code "335") (name "A7") (class "Default")
      (node (ref "CONN1") (pin "54") (pinfunction "54_54") (pintype "passive"))
      (node (ref "U2A") (pin "3") (pinfunction "A7_3") (pintype "input"))
      (node (ref "U2B") (pin "3") (pinfunction "A7_3") (pintype "input"))
      (node (ref "U2C") (pin "3") (pinfunction "A7_3") (pintype "input"))
      (node (ref "U2D") (pin "3") (pinfunction "A7_3") (pintype "input"))
      (node (ref "U2E") (pin "1") (pinfunction "A7_1") (pintype "input"))
      (node (ref "U3B") (pin "13") (pinfunction "4B_13") (pintype "input"))
    )
    (net (code "336") (name "A8") (class "Default")
      (node (ref "CONN1") (pin "51") (pinfunction "51_51") (pintype "passive"))
      (node (ref "U2A") (pin "25") (pinfunction "A8_25") (pintype "input"))
      (node (ref "U2B") (pin "25") (pinfunction "A8_25") (pintype "input"))
      (node (ref "U2C") (pin "25") (pinfunction "A8_25") (pintype "input"))
      (node (ref "U2D") (pin "25") (pinfunction "A8_25") (pintype "input"))
      (node (ref "U2E") (pin "23") (pinfunction "A8_23") (pintype "input"))
      (node (ref "U3C") (pin "3") (pinfunction "1B_3") (pintype "input"))
    )
    (net (code "337") (name "A9") (class "Default")
      (node (ref "CONN1") (pin "49") (pinfunction "49_49") (pintype "passive"))
      (node (ref "U2A") (pin "24") (pinfunction "A9_24") (pintype "input"))
      (node (ref "U2B") (pin "24") (pinfunction "A9_24") (pintype "input"))
      (node (ref "U2C") (pin "24") (pinfunction "A9_24") (pintype "input"))
      (node (ref "U2D") (pin "24") (pinfunction "A9_24") (pintype "input"))
      (node (ref "U2E") (pin "22") (pinfunction "A9_22") (pintype "input"))
      (node (ref "U3C") (pin "6") (pinfunction "2B_6") (pintype "input"))
    )
    (net (code "338") (name "A10") (class "Default")
      (node (ref "CONN1") (pin "46") (pinfunction "46_46") (pintype "passive"))
      (node (ref "U2A") (pin "21") (pinfunction "A10_21") (pintype "input"))
      (node (ref "U2B") (pin "21") (pinfunction "A10_21") (pintype "input"))
      (node (ref "U2C") (pin "21") (pinfunction "A10_21") (pintype "input"))
      (node (ref "U2D") (pin "21") (pinfunction "A10_21") (pintype "input"))
      (node (ref "U2E") (pin "19") (pinfunction "A10_19") (pintype "input"))
      (node (ref "U3C") (pin "10") (pinfunction "3B_10") (pintype "input"))
    )
    (net (code "339") (name "A11") (class "Default")
      (node (ref "CONN1") (pin "44") (pinfunction "44_44") (pintype "passive"))
      (node (ref "U2A") (pin "23") (pinfunction "A11_23") (pintype "input"))
      (node (ref "U2B") (pin "23") (pinfunction "A11_23") (pintype "input"))
      (node (ref "U2C") (pin "23") (pinfunction "A11_23") (pintype "input"))
      (node (ref "U2D") (pin "23") (pinfunction "A11_23") (pintype "input"))
      (node (ref "U3C") (pin "13") (pinfunction "4B_13") (pintype "input"))
    )
    (net (code "340") (name "A12") (class "Default")
      (node (ref "CONN1") (pin "47") (pinfunction "47_47") (pintype "passive"))
      (node (ref "U2A") (pin "2") (pinfunction "A12_2") (pintype "input"))
      (node (ref "U2B") (pin "2") (pinfunction "A12_2") (pintype "input"))
      (node (ref "U2C") (pin "2") (pinfunction "A12_2") (pintype "input"))
      (node (ref "U2D") (pin "2") (pinfunction "A12_2") (pintype "input"))
      (node (ref "U3D") (pin "3") (pinfunction "1B_3") (pintype "input"))
      (node (ref "U8A") (pin "41") (pinfunction "MC49_41") (pintype "bidirectional"))
    )
    (net (code "341") (name "A13") (class "Default")
      (node (ref "CONN1") (pin "37") (pinfunction "37_37") (pintype "passive"))
      (node (ref "U3D") (pin "6") (pinfunction "2B_6") (pintype "input"))
      (node (ref "U8A") (pin "40") (pinfunction "MC51_40") (pintype "bidirectional"))
    )
    (net (code "342") (name "A14") (class "Default")
      (node (ref "CONN1") (pin "39") (pinfunction "39_39") (pintype "passive"))
      (node (ref "U3D") (pin "10") (pinfunction "3B_10") (pintype "input"))
      (node (ref "U8A") (pin "39") (pinfunction "MC53_39") (pintype "bidirectional"))
    )
    (net (code "343") (name "A15") (class "Default")
      (node (ref "CONN1") (pin "40") (pinfunction "40_40") (pintype "passive"))
      (node (ref "U3D") (pin "13") (pinfunction "4B_13") (pintype "input"))
      (node (ref "U8A") (pin "37") (pinfunction "MC56_37") (pintype "bidirectional"))
    )
    (net (code "344") (name "A16") (class "Default")
      (node (ref "CONN1") (pin "53") (pinfunction "53_53") (pintype "passive"))
      (node (ref "U4A") (pin "2") (pinfunction "A16_2") (pintype "input"))
      (node (ref "U4B") (pin "2") (pinfunction "A16_2") (pintype "input"))
      (node (ref "U8A") (pin "36") (pinfunction "MC57_36") (pintype "bidirectional"))
    )
    (net (code "345") (name "A17") (class "Default")
      (node (ref "CONN1") (pin "55") (pinfunction "55_55") (pintype "passive"))
      (node (ref "U4A") (pin "30") (pinfunction "A17_30") (pintype "input"))
      (node (ref "U4B") (pin "30") (pinfunction "A17_30") (pintype "input"))
      (node (ref "U8A") (pin "35") (pinfunction "MC59_35") (pintype "bidirectional"))
    )
    (net (code "346") (name "A18") (class "Default")
      (node (ref "CONN1") (pin "56") (pinfunction "56_56") (pintype "passive"))
      (node (ref "U4A") (pin "1") (pinfunction "A18_1") (pintype "input"))
      (node (ref "U4B") (pin "1") (pinfunction "A18_1") (pintype "input"))
      (node (ref "U8A") (pin "34") (pinfunction "MC61_34") (pintype "bidirectional"))
    )
    (net (code "347") (name "A19") (class "Default")
      (node (ref "CONN1") (pin "58") (pinfunction "58_58") (pintype "passive"))
      (node (ref "U8A") (pin "33") (pinfunction "MC64_33") (pintype "bidirectional"))
    )
    (net (code "348") (name "AA8") (class "Default")
      (node (ref "U5A") (pin "8") (pinfunction "A8_8") (pintype "bidirectional"))
      (node (ref "U5B") (pin "8") (pinfunction "AD8_8") (pintype "bidirectional"))
      (node (ref "U7B") (pin "3") (pinfunction "1D_3") (pintype "input"))
    )
    (net (code "349") (name "AA9") (class "Default")
      (node (ref "U5A") (pin "7") (pinfunction "A9_7") (pintype "bidirectional"))
      (node (ref "U5B") (pin "7") (pinfunction "AD9_7") (pintype "bidirectional"))
      (node (ref "U7B") (pin "4") (pinfunction "2D_4") (pintype "input"))
    )
    (net (code "350") (name "AA10") (class "Default")
      (node (ref "U5A") (pin "6") (pinfunction "A10_6") (pintype "bidirectional"))
      (node (ref "U5B") (pin "6") (pinfunction "AD10_6") (pintype "bidirectional"))
      (node (ref "U7B") (pin "7") (pinfunction "3D_7") (pintype "input"))
    )
    (net (code "351") (name "AA11") (class "Default")
      (node (ref "U5A") (pin "5") (pinfunction "A11_5") (pintype "bidirectional"))
      (node (ref "U5B") (pin "5") (pinfunction "AD11_5") (pintype "bidirectional"))
      (node (ref "U7B") (pin "8") (pinfunction "4D_8") (pintype "input"))
    )
    (net (code "352") (name "AA12") (class "Default")
      (node (ref "U5A") (pin "4") (pinfunction "A12_4") (pintype "bidirectional"))
      (node (ref "U5B") (pin "4") (pinfunction "AD12_4") (pintype "bidirectional"))
      (node (ref "U7B") (pin "13") (pinfunction "5D_13") (pintype "input"))
    )
    (net (code "353") (name "AA13") (class "Default")
      (node (ref "U5A") (pin "3") (pinfunction "A13_3") (pintype "bidirectional"))
      (node (ref "U5B") (pin "3") (pinfunction "AD13_3") (pintype "bidirectional"))
      (node (ref "U7B") (pin "14") (pinfunction "6D_14") (pintype "input"))
    )
    (net (code "354") (name "AA14") (class "Default")
      (node (ref "U5A") (pin "2") (pinfunction "A14_2") (pintype "bidirectional"))
      (node (ref "U5B") (pin "2") (pinfunction "AD14_2") (pintype "bidirectional"))
      (node (ref "U7B") (pin "17") (pinfunction "7D_17") (pintype "input"))
    )
    (net (code "355") (name "AA15") (class "Default")
      (node (ref "U5A") (pin "39") (pinfunction "A15_39") (pintype "bidirectional"))
      (node (ref "U5B") (pin "39") (pinfunction "AD15_39") (pintype "bidirectional"))
      (node (ref "U7B") (pin "18") (pinfunction "8D_18") (pintype "input"))
    )
    (net (code "356") (name "AA16") (class "Default")
      (node (ref "U5A") (pin "38") (pinfunction "A16/S3_38") (pintype "output"))
      (node (ref "U5B") (pin "38") (pinfunction "A16/S3_38") (pintype "bidirectional"))
      (node (ref "U7C") (pin "3") (pinfunction "1D_3") (pintype "input"))
    )
    (net (code "357") (name "AA17") (class "Default")
      (node (ref "U5A") (pin "37") (pinfunction "A17/S4_37") (pintype "output"))
      (node (ref "U5B") (pin "37") (pinfunction "A17/S4_37") (pintype "bidirectional"))
      (node (ref "U7C") (pin "4") (pinfunction "2D_4") (pintype "input"))
    )
    (net (code "358") (name "AA18") (class "Default")
      (node (ref "U5A") (pin "36") (pinfunction "A18/S5_36") (pintype "output"))
      (node (ref "U5B") (pin "36") (pinfunction "A18/S5_36") (pintype "bidirectional"))
      (node (ref "U7C") (pin "7") (pinfunction "3D_7") (pintype "input"))
    )
    (net (code "359") (name "AA19") (class "Default")
      (node (ref "U5A") (pin "35") (pinfunction "A19/S6_35") (pintype "output"))
      (node (ref "U5B") (pin "35") (pinfunction "A19/S6_35") (pintype "bidirectional"))
      (node (ref "U7C") (pin "8") (pinfunction "4D_8") (pintype "input"))
    )
    (net (code "360") (name "AD0") (class "Default")
      (node (ref "CONN5") (pin "16") (pinfunction "16_16") (pintype "passive"))
      (node (ref "U4C") (pin "2") (pinfunction "A1_2") (pintype "bidirectional"))
      (node (ref "U5A") (pin "16") (pinfunction "AD0_16") (pintype "bidirectional"))
      (node (ref "U5B") (pin "16") (pinfunction "AD0_16") (pintype "bidirectional"))
      (node (ref "U6B") (pin "34") (pinfunction "D0_34") (pintype "bidirectional"))
      (node (ref "U6C") (pin "11") (pinfunction "D0_11") (pintype "bidirectional"))
      (node (ref "U7A") (pin "3") (pinfunction "1D_3") (pintype "input"))
      (node (ref "U7D") (pin "11") (pinfunction "O0_11") (pintype "tri_state"))
      (node (ref "U8A") (pin "31") (pinfunction "MC35_31") (pintype "bidirectional"))
    )
    (net (code "361") (name "AD1") (class "Default")
      (node (ref "CONN5") (pin "14") (pinfunction "14_14") (pintype "passive"))
      (node (ref "U4C") (pin "3") (pinfunction "A2_3") (pintype "bidirectional"))
      (node (ref "U5A") (pin "15") (pinfunction "AD1_15") (pintype "bidirectional"))
      (node (ref "U5B") (pin "15") (pinfunction "AD1_15") (pintype "bidirectional"))
      (node (ref "U6B") (pin "33") (pinfunction "D1_33") (pintype "bidirectional"))
      (node (ref "U6C") (pin "10") (pinfunction "D1_10") (pintype "bidirectional"))
      (node (ref "U7A") (pin "4") (pinfunction "2D_4") (pintype "input"))
      (node (ref "U7D") (pin "12") (pinfunction "O1_12") (pintype "tri_state"))
      (node (ref "U8A") (pin "30") (pinfunction "MC37_30") (pintype "bidirectional"))
    )
    (net (code "362") (name "AD2") (class "Default")
      (node (ref "CONN5") (pin "12") (pinfunction "12_12") (pintype "passive"))
      (node (ref "U4C") (pin "4") (pinfunction "A3_4") (pintype "bidirectional"))
      (node (ref "U5A") (pin "14") (pinfunction "AD2_14") (pintype "bidirectional"))
      (node (ref "U5B") (pin "14") (pinfunction "AD2_14") (pintype "bidirectional"))
      (node (ref "U6B") (pin "32") (pinfunction "D2_32") (pintype "bidirectional"))
      (node (ref "U6C") (pin "9") (pinfunction "D2_9") (pintype "bidirectional"))
      (node (ref "U7A") (pin "7") (pinfunction "3D_7") (pintype "input"))
      (node (ref "U7D") (pin "13") (pinfunction "O2_13") (pintype "tri_state"))
      (node (ref "U8A") (pin "29") (pinfunction "MC38_29") (pintype "bidirectional"))
    )
    (net (code "363") (name "AD3") (class "Default")
      (node (ref "CONN5") (pin "10") (pinfunction "10_10") (pintype "passive"))
      (node (ref "U4C") (pin "5") (pinfunction "A4_5") (pintype "bidirectional"))
      (node (ref "U5A") (pin "13") (pinfunction "AD3_13") (pintype "bidirectional"))
      (node (ref "U5B") (pin "13") (pinfunction "AD3_13") (pintype "bidirectional"))
      (node (ref "U6B") (pin "31") (pinfunction "D3_31") (pintype "bidirectional"))
      (node (ref "U6C") (pin "8") (pinfunction "D3_8") (pintype "bidirectional"))
      (node (ref "U7A") (pin "8") (pinfunction "4D_8") (pintype "input"))
      (node (ref "U7D") (pin "15") (pinfunction "O3_15") (pintype "tri_state"))
      (node (ref "U8A") (pin "28") (pinfunction "MC40_28") (pintype "bidirectional"))
    )
    (net (code "364") (name "AD4") (class "Default")
      (node (ref "CONN5") (pin "8") (pinfunction "8_8") (pintype "passive"))
      (node (ref "U4C") (pin "6") (pinfunction "A5_6") (pintype "bidirectional"))
      (node (ref "U5A") (pin "12") (pinfunction "AD4_12") (pintype "bidirectional"))
      (node (ref "U5B") (pin "12") (pinfunction "AD4_12") (pintype "bidirectional"))
      (node (ref "U6B") (pin "30") (pinfunction "D4_30") (pintype "bidirectional"))
      (node (ref "U6C") (pin "7") (pinfunction "D4_7") (pintype "bidirectional"))
      (node (ref "U7A") (pin "13") (pinfunction "5D_13") (pintype "input"))
      (node (ref "U7D") (pin "16") (pinfunction "O4_16") (pintype "tri_state"))
      (node (ref "U8A") (pin "27") (pinfunction "MC43_27") (pintype "bidirectional"))
    )
    (net (code "365") (name "AD5") (class "Default")
      (node (ref "CONN5") (pin "6") (pinfunction "6_6") (pintype "passive"))
      (node (ref "U4C") (pin "7") (pinfunction "A6_7") (pintype "bidirectional"))
      (node (ref "U5A") (pin "11") (pinfunction "AD5_11") (pintype "bidirectional"))
      (node (ref "U5B") (pin "11") (pinfunction "AD5_11") (pintype "bidirectional"))
      (node (ref "U6B") (pin "29") (pinfunction "D5_29") (pintype "bidirectional"))
      (node (ref "U6C") (pin "6") (pinfunction "D5_6") (pintype "bidirectional"))
      (node (ref "U7A") (pin "14") (pinfunction "6D_14") (pintype "input"))
      (node (ref "U7D") (pin "17") (pinfunction "O5_17") (pintype "tri_state"))
      (node (ref "U8A") (pin "25") (pinfunction "MC45_25") (pintype "bidirectional"))
    )
    (net (code "366") (name "AD6") (class "Default")
      (node (ref "CONN5") (pin "4") (pinfunction "4_4") (pintype "passive"))
      (node (ref "U4C") (pin "8") (pinfunction "A7_8") (pintype "bidirectional"))
      (node (ref "U5A") (pin "10") (pinfunction "AD6_10") (pintype "bidirectional"))
      (node (ref "U5B") (pin "10") (pinfunction "AD6_10") (pintype "bidirectional"))
      (node (ref "U6B") (pin "28") (pinfunction "D6_28") (pintype "bidirectional"))
      (node (ref "U6C") (pin "5") (pinfunction "D6_5") (pintype "bidirectional"))
      (node (ref "U7A") (pin "17") (pinfunction "7D_17") (pintype "input"))
      (node (ref "U7D") (pin "18") (pinfunction "O6_18") (pintype "tri_state"))
      (node (ref "U8A") (pin "24") (pinfunction "MC46_24") (pintype "bidirectional"))
    )
    (net (code "367") (name "AD7") (class "Default")
      (node (ref "CONN5") (pin "2") (pinfunction "2_2") (pintype "passive"))
      (node (ref "U4C") (pin "9") (pinfunction "A8_9") (pintype "bidirectional"))
      (node (ref "U5A") (pin "9") (pinfunction "AD7_9") (pintype "bidirectional"))
      (node (ref "U5B") (pin "9") (pinfunction "AD7_9") (pintype "bidirectional"))
      (node (ref "U6B") (pin "27") (pinfunction "D7_27") (pintype "bidirectional"))
      (node (ref "U6C") (pin "4") (pinfunction "D7_4") (pintype "bidirectional"))
      (node (ref "U7A") (pin "18") (pinfunction "8D_18") (pintype "input"))
      (node (ref "U7D") (pin "19") (pinfunction "O7_19") (pintype "tri_state"))
      (node (ref "U8A") (pin "22") (pinfunction "MC17_22") (pintype "bidirectional"))
    )
    (net (code "368") (name "ALE") (class "Default")
      (node (ref "CONN5") (pin "53") (pinfunction "53_53") (pintype "passive"))
      (node (ref "RN2") (pin "4") (pinfunction "2_4") (pintype "passive"))
      (node (ref "U5C") (pin "5") (pinfunction "ALE_5") (pintype "output"))
      (node (ref "U7A") (pin "11") (pinfunction "ENC_11") (pintype "input"))
      (node (ref "U7B") (pin "11") (pinfunction "ENC_11") (pintype "input"))
      (node (ref "U7C") (pin "11") (pinfunction "ENC_11") (pintype "input"))
      (node (ref "U8A") (pin "81") (pinfunction "GCLK3/MC128_81") (pintype "bidirectional"))
    )
    (net (code "369") (name "CLK") (class "Default")
      (node (ref "CONN5") (pin "37") (pinfunction "37_37") (pintype "passive"))
      (node (ref "U5A") (pin "19") (pinfunction "CLK_19") (pintype "input"))
      (node (ref "U5B") (pin "19") (pinfunction "CLK_19") (pintype "input"))
      (node (ref "U5C") (pin "2") (pinfunction "CLK_2") (pintype "input"))
      (node (ref "U8A") (pin "73") (pinfunction "MC115_73") (pintype "bidirectional"))
    )
    (net (code "370") (name "CS'") (class "Default")
      (node (ref "J1") (pin "1") (pinfunction "CD/DAT3/CS_1") (pintype "bidirectional"))
      (node (ref "U10A") (pin "6") (pinfunction "O_6") (pintype "output"))
    )
    (net (code "371") (name "D0") (class "Default")
      (node (ref "CONN1") (pin "36") (pinfunction "36_36") (pintype "passive"))
      (node (ref "U2A") (pin "11") (pinfunction "I/O1_11") (pintype "bidirectional"))
      (node (ref "U2B") (pin "11") (pinfunction "I/O1_11") (pintype "bidirectional"))
      (node (ref "U2C") (pin "11") (pinfunction "I/O1_11") (pintype "bidirectional"))
      (node (ref "U2D") (pin "11") (pinfunction "I/O1_11") (pintype "bidirectional"))
      (node (ref "U2E") (pin "9") (pinfunction "D0_9") (pintype "bidirectional"))
      (node (ref "U6A") (pin "33") (pinfunction "D0_33") (pintype "bidirectional"))
    )
    (net (code "372") (name "D1") (class "Default")
      (node (ref "CONN1") (pin "34") (pinfunction "34_34") (pintype "passive"))
      (node (ref "U2A") (pin "12") (pinfunction "I/O2_12") (pintype "bidirectional"))
      (node (ref "U2B") (pin "12") (pinfunction "I/O2_12") (pintype "bidirectional"))
      (node (ref "U2C") (pin "12") (pinfunction "I/O2_12") (pintype "bidirectional"))
      (node (ref "U2D") (pin "12") (pinfunction "I/O2_12") (pintype "bidirectional"))
      (node (ref "U2E") (pin "10") (pinfunction "D1_10") (pintype "bidirectional"))
      (node (ref "U6A") (pin "32") (pinfunction "D1_32") (pintype "bidirectional"))
    )
    (net (code "373") (name "D2") (class "Default")
      (node (ref "CONN1") (pin "32") (pinfunction "32_32") (pintype "passive"))
      (node (ref "U2A") (pin "13") (pinfunction "I/O3_13") (pintype "bidirectional"))
      (node (ref "U2B") (pin "13") (pinfunction "I/O3_13") (pintype "bidirectional"))
      (node (ref "U2C") (pin "13") (pinfunction "I/O3_13") (pintype "bidirectional"))
      (node (ref "U2D") (pin "13") (pinfunction "I/O3_13") (pintype "bidirectional"))
      (node (ref "U2E") (pin "11") (pinfunction "D2_11") (pintype "bidirectional"))
      (node (ref "U6A") (pin "31") (pinfunction "D2_31") (pintype "bidirectional"))
    )
    (net (code "374") (name "D3") (class "Default")
      (node (ref "CONN1") (pin "29") (pinfunction "29_29") (pintype "passive"))
      (node (ref "U2A") (pin "15") (pinfunction "I/O4_15") (pintype "bidirectional"))
      (node (ref "U2B") (pin "15") (pinfunction "I/O4_15") (pintype "bidirectional"))
      (node (ref "U2C") (pin "15") (pinfunction "I/O4_15") (pintype "bidirectional"))
      (node (ref "U2D") (pin "15") (pinfunction "I/O4_15") (pintype "bidirectional"))
      (node (ref "U2E") (pin "13") (pinfunction "D3_13") (pintype "bidirectional"))
      (node (ref "U6A") (pin "30") (pinfunction "D3_30") (pintype "bidirectional"))
    )
    (net (code "375") (name "D4") (class "Default")
      (node (ref "CONN1") (pin "31") (pinfunction "31_31") (pintype "passive"))
      (node (ref "U2A") (pin "16") (pinfunction "I/O5_16") (pintype "bidirectional"))
      (node (ref "U2B") (pin "16") (pinfunction "I/O5_16") (pintype "bidirectional"))
      (node (ref "U2C") (pin "16") (pinfunction "I/O5_16") (pintype "bidirectional"))
      (node (ref "U2D") (pin "16") (pinfunction "I/O5_16") (pintype "bidirectional"))
      (node (ref "U2E") (pin "14") (pinfunction "D4_14") (pintype "bidirectional"))
      (node (ref "U6A") (pin "29") (pinfunction "D4_29") (pintype "bidirectional"))
    )
    (net (code "376") (name "D5") (class "Default")
      (node (ref "CONN1") (pin "33") (pinfunction "33_33") (pintype "passive"))
      (node (ref "U2A") (pin "17") (pinfunction "I/O6_17") (pintype "bidirectional"))
      (node (ref "U2B") (pin "17") (pinfunction "I/O6_17") (pintype "bidirectional"))
      (node (ref "U2C") (pin "17") (pinfunction "I/O6_17") (pintype "bidirectional"))
      (node (ref "U2D") (pin "17") (pinfunction "I/O6_17") (pintype "bidirectional"))
      (node (ref "U2E") (pin "15") (pinfunction "D5_15") (pintype "bidirectional"))
      (node (ref "U6A") (pin "28") (pinfunction "D5_28") (pintype "bidirectional"))
    )
    (net (code "377") (name "D6") (class "Default")
      (node (ref "CONN1") (pin "35") (pinfunction "35_35") (pintype "passive"))
      (node (ref "U2A") (pin "18") (pinfunction "I/O7_18") (pintype "bidirectional"))
      (node (ref "U2B") (pin "18") (pinfunction "I/O7_18") (pintype "bidirectional"))
      (node (ref "U2C") (pin "18") (pinfunction "I/O7_18") (pintype "bidirectional"))
      (node (ref "U2D") (pin "18") (pinfunction "I/O7_18") (pintype "bidirectional"))
      (node (ref "U2E") (pin "16") (pinfunction "D6_16") (pintype "bidirectional"))
      (node (ref "U6A") (pin "27") (pinfunction "D6_27") (pintype "bidirectional"))
    )
    (net (code "378") (name "D7") (class "Default")
      (node (ref "CONN1") (pin "38") (pinfunction "38_38") (pintype "passive"))
      (node (ref "U2A") (pin "19") (pinfunction "I/O8_19") (pintype "bidirectional"))
      (node (ref "U2B") (pin "19") (pinfunction "I/O8_19") (pintype "bidirectional"))
      (node (ref "U2C") (pin "19") (pinfunction "I/O8_19") (pintype "bidirectional"))
      (node (ref "U2D") (pin "19") (pinfunction "I/O8_19") (pintype "bidirectional"))
      (node (ref "U2E") (pin "17") (pinfunction "D7_17") (pintype "bidirectional"))
      (node (ref "U6A") (pin "26") (pinfunction "D7_26") (pintype "bidirectional"))
    )
    (net (code "379") (name "DEN") (class "Default")
      (node (ref "RN2") (pin "3") (pinfunction "2_3") (pintype "passive"))
      (node (ref "U5C") (pin "16") (pinfunction "DEN_16") (pintype "output"))
      (node (ref "U8A") (pin "75") (pinfunction "MC118_75") (pintype "bidirectional"))
    )
    (net (code "380") (name "DT{slash}R") (class "Default")
      (node (ref "RN2") (pin "2") (pinfunction "2_2") (pintype "passive"))
      (node (ref "U4C") (pin "1") (pinfunction "DIR_1") (pintype "input"))
      (node (ref "U5C") (pin "4") (pinfunction "DT/~{R}_4") (pintype "output"))
    )
    (net (code "381") (name "GND") (class "Default")
      (node (ref "C10A") (pin "2") (pinfunction "2_2") (pintype "passive"))
      (node (ref "C10B") (pin "2") (pinfunction "2_2") (pintype "passive"))
      (node (ref "C10C") (pin "2") (pinfunction "2_2") (pintype "passive"))
      (node (ref "C10D") (pin "2") (pinfunction "2_2") (pintype "passive"))
      (node (ref "C10E") (pin "-") (pinfunction "-_-") (pintype "passive"))
      (node (ref "C2A") (pin "2") (pinfunction "2_2") (pintype "passive"))
      (node (ref "C2B") (pin "2") (pinfunction "2_2") (pintype "passive"))
      (node (ref "C2C") (pin "2") (pinfunction "2_2") (pintype "passive"))
      (node (ref "C2D") (pin "2") (pinfunction "2_2") (pintype "passive"))
      (node (ref "C2E") (pin "2") (pinfunction "2_2") (pintype "passive"))
      (node (ref "C3A") (pin "2") (pinfunction "2_2") (pintype "passive"))
      (node (ref "C3B") (pin "2") (pinfunction "2_2") (pintype "passive"))
      (node (ref "C3C") (pin "2") (pinfunction "2_2") (pintype "passive"))
      (node (ref "C3D") (pin "2") (pinfunction "2_2") (pintype "passive"))
      (node (ref "C4A") (pin "2") (pinfunction "2_2") (pintype "passive"))
      (node (ref "C4B") (pin "2") (pinfunction "2_2") (pintype "passive"))
      (node (ref "C4C") (pin "2") (pinfunction "2_2") (pintype "passive"))
      (node (ref "C5A") (pin "2") (pinfunction "2_2") (pintype "passive"))
      (node (ref "C5B") (pin "2") (pinfunction "2_2") (pintype "passive"))
      (node (ref "C5C") (pin "2") (pinfunction "2_2") (pintype "passive"))
      (node (ref "C6A") (pin "2") (pinfunction "2_2") (pintype "passive"))
      (node (ref "C6B") (pin "2") (pinfunction "2_2") (pintype "passive"))
      (node (ref "C6C") (pin "2") (pinfunction "2_2") (pintype "passive"))
      (node (ref "C7A") (pin "2") (pinfunction "2_2") (pintype "passive"))
      (node (ref "C7B") (pin "2") (pinfunction "2_2") (pintype "passive"))
      (node (ref "C7C") (pin "2") (pinfunction "2_2") (pintype "passive"))
      (node (ref "C7D") (pin "2") (pinfunction "2_2") (pintype "passive"))
      (node (ref "C8A") (pin "-") (pinfunction "-_-") (pintype "passive"))
      (node (ref "CONN1") (pin "10") (pinfunction "10_10") (pintype "passive"))
      (node (ref "CONN1") (pin "5") (pinfunction "5_5") (pintype "passive"))
      (node (ref "CONN1") (pin "6") (pinfunction "6_6") (pintype "passive"))
      (node (ref "CONN1") (pin "7") (pinfunction "7_7") (pintype "passive"))
      (node (ref "CONN1") (pin "8") (pinfunction "8_8") (pintype "passive"))
      (node (ref "CONN1") (pin "9") (pinfunction "9_9") (pintype "passive"))
      (node (ref "CONN2") (pin "17") (pinfunction "17_17") (pintype "passive"))
      (node (ref "CONN2") (pin "18") (pinfunction "18_18") (pintype "passive"))
      (node (ref "CONN2") (pin "19") (pinfunction "19_19") (pintype "passive"))
      (node (ref "CONN2") (pin "20") (pinfunction "20_20") (pintype "passive"))
      (node (ref "CONN2") (pin "21") (pinfunction "21_21") (pintype "passive"))
      (node (ref "CONN2") (pin "23") (pinfunction "23_23") (pintype "passive"))
      (node (ref "CONN2") (pin "25") (pinfunction "25_25") (pintype "passive"))
      (node (ref "CONN2") (pin "27") (pinfunction "27_27") (pintype "passive"))
      (node (ref "CONN2") (pin "29") (pinfunction "29_29") (pintype "passive"))
      (node (ref "CONN2") (pin "31") (pinfunction "31_31") (pintype "passive"))
      (node (ref "CONN3") (pin "9") (pinfunction "9_9") (pintype "passive"))
      (node (ref "CONN4") (pin "1") (pinfunction "1_1") (pintype "passive"))
      (node (ref "CONN4") (pin "9") (pinfunction "9_9") (pintype "passive"))
      (node (ref "CONN5") (pin "59") (pinfunction "59_59") (pintype "passive"))
      (node (ref "G1") (pin "-") (pinfunction "-_-") (pintype "passive"))
      (node (ref "IC1") (pin "2") (pinfunction "GND_2") (pintype "power_in"))
      (node (ref "J1") (pin "3") (pinfunction "VSS1_3") (pintype "power_in"))
      (node (ref "J1") (pin "6") (pinfunction "VSS2_6") (pintype "power_in"))
      (node (ref "J1") (pin "M1") (pinfunction "GND_M1") (pintype "power_in"))
      (node (ref "J1") (pin "M2") (pinfunction "GND_M2") (pintype "power_in"))
      (node (ref "J1") (pin "M3") (pinfunction "GND_M3") (pintype "power_in"))
      (node (ref "J1") (pin "M4") (pinfunction "GND_M4") (pintype "power_in"))
      (node (ref "LED2") (pin "K") (pinfunction "C_K") (pintype "passive"))
      (node (ref "R1") (pin "1") (pinfunction "1_1") (pintype "passive"))
      (node (ref "U10A") (pin "8") (pinfunction "VSS_8") (pintype "power_in"))
      (node (ref "U10B") (pin "4") (pinfunction "GND_4") (pintype "power_in"))
      (node (ref "U10C") (pin "2") (pinfunction "A1_2") (pintype "input"))
      (node (ref "U10C") (pin "3") (pinfunction "A2_3") (pintype "input"))
      (node (ref "U10C") (pin "4") (pinfunction "GND_4") (pintype "power_in"))
      (node (ref "U10C") (pin "7") (pinfunction "WP_7") (pintype "input"))
      (node (ref "U2A") (pin "14") (pinfunction "VSS_14") (pintype "power_in"))
      (node (ref "U2A") (pin "22") (pinfunction "~{OE}_22") (pintype "input"))
      (node (ref "U2B") (pin "14") (pinfunction "VSS_14") (pintype "power_in"))
      (node (ref "U2B") (pin "22") (pinfunction "~{OE}_22") (pintype "input"))
      (node (ref "U2C") (pin "14") (pinfunction "VSS_14") (pintype "power_in"))
      (node (ref "U2C") (pin "22") (pinfunction "~{OE}_22") (pintype "input"))
      (node (ref "U2D") (pin "14") (pinfunction "VSS_14") (pintype "power_in"))
      (node (ref "U2D") (pin "22") (pinfunction "~{OE}_22") (pintype "input"))
      (node (ref "U2E") (pin "20") (pinfunction "~{OE}_20") (pintype "input"))
      (node (ref "U3A") (pin "15") (pinfunction "G_15") (pintype "input"))
      (node (ref "U3B") (pin "15") (pinfunction "G_15") (pintype "input"))
      (node (ref "U3C") (pin "15") (pinfunction "G_15") (pintype "input"))
      (node (ref "U3D") (pin "15") (pinfunction "G_15") (pintype "input"))
      (node (ref "U4A") (pin "16") (pinfunction "VSS_16") (pintype "power_in"))
      (node (ref "U4B") (pin "16") (pinfunction "VSS_16") (pintype "power_in"))
      (node (ref "U5A") (pin "33") (pinfunction "~{MX}_33") (pintype "input"))
      (node (ref "U5C") (pin "6") (pinfunction "~{AEN}_6") (pintype "input"))
      (node (ref "U7A") (pin "1") (pinfunction "OC_1") (pintype "input"))
      (node (ref "U7B") (pin "1") (pinfunction "OC_1") (pintype "input"))
      (node (ref "U7C") (pin "1") (pinfunction "OC_1") (pintype "input"))
      (node (ref "U8A") (pin "19") (pinfunction "GND_19") (pintype "bidirectional"))
      (node (ref "U8A") (pin "32") (pinfunction "GND_32") (pintype "bidirectional"))
      (node (ref "U8A") (pin "42") (pinfunction "GND_42") (pintype "bidirectional"))
      (node (ref "U8A") (pin "47") (pinfunction "GND_47") (pintype "bidirectional"))
      (node (ref "U8A") (pin "59") (pinfunction "GND_59") (pintype "bidirectional"))
      (node (ref "U8A") (pin "7") (pinfunction "GND_7") (pintype "bidirectional"))
      (node (ref "U8A") (pin "72") (pinfunction "GND_72") (pintype "bidirectional"))
      (node (ref "U8A") (pin "82") (pinfunction "GND_82") (pintype "bidirectional"))
      (node (ref "XTAL1") (pin "7") (pinfunction "VSS_7") (pintype "power_in"))
    )
    (net (code "382") (name "IA0") (class "Default")
      (node (ref "CONN5") (pin "60") (pinfunction "60_60") (pintype "passive"))
      (node (ref "U3A") (pin "2") (pinfunction "1A_2") (pintype "input"))
      (node (ref "U6B") (pin "9") (pinfunction "A0_9") (pintype "input"))
      (node (ref "U6C") (pin "27") (pinfunction "A0_27") (pintype "input"))
      (node (ref "U7A") (pin "2") (pinfunction "1Q_2") (pintype "tri_state"))
      (node (ref "U7D") (pin "10") (pinfunction "A0_10") (pintype "input"))
    )
    (net (code "383") (name "IA1") (class "Default")
      (node (ref "CONN5") (pin "58") (pinfunction "58_58") (pintype "passive"))
      (node (ref "U3A") (pin "5") (pinfunction "2A_5") (pintype "input"))
      (node (ref "U6B") (pin "8") (pinfunction "A1_8") (pintype "input"))
      (node (ref "U7A") (pin "5") (pinfunction "2Q_5") (pintype "tri_state"))
      (node (ref "U7D") (pin "9") (pinfunction "A1_9") (pintype "input"))
    )
    (net (code "384") (name "IA2") (class "Default")
      (node (ref "CONN5") (pin "56") (pinfunction "56_56") (pintype "passive"))
      (node (ref "U3A") (pin "11") (pinfunction "3A_11") (pintype "input"))
      (node (ref "U7A") (pin "6") (pinfunction "3Q_6") (pintype "tri_state"))
      (node (ref "U7D") (pin "8") (pinfunction "A2_8") (pintype "input"))
    )
    (net (code "385") (name "IA3") (class "Default")
      (node (ref "CONN5") (pin "54") (pinfunction "54_54") (pintype "passive"))
      (node (ref "U3A") (pin "14") (pinfunction "4A_14") (pintype "input"))
      (node (ref "U7A") (pin "9") (pinfunction "4Q_9") (pintype "tri_state"))
      (node (ref "U7D") (pin "7") (pinfunction "A3_7") (pintype "input"))
    )
    (net (code "386") (name "IA4") (class "Default")
      (node (ref "CONN5") (pin "52") (pinfunction "52_52") (pintype "passive"))
      (node (ref "U3B") (pin "2") (pinfunction "1A_2") (pintype "input"))
      (node (ref "U7A") (pin "12") (pinfunction "5Q_12") (pintype "tri_state"))
      (node (ref "U7D") (pin "6") (pinfunction "A4_6") (pintype "input"))
    )
    (net (code "387") (name "IA5") (class "Default")
      (node (ref "CONN5") (pin "50") (pinfunction "50_50") (pintype "passive"))
      (node (ref "U3B") (pin "5") (pinfunction "2A_5") (pintype "input"))
      (node (ref "U7A") (pin "15") (pinfunction "6Q_15") (pintype "tri_state"))
      (node (ref "U7D") (pin "5") (pinfunction "A5_5") (pintype "input"))
    )
    (net (code "388") (name "IA6") (class "Default")
      (node (ref "CONN5") (pin "48") (pinfunction "48_48") (pintype "passive"))
      (node (ref "U3B") (pin "11") (pinfunction "3A_11") (pintype "input"))
      (node (ref "U7A") (pin "16") (pinfunction "7Q_16") (pintype "tri_state"))
      (node (ref "U7D") (pin "4") (pinfunction "A6_4") (pintype "input"))
    )
    (net (code "389") (name "IA7") (class "Default")
      (node (ref "CONN5") (pin "46") (pinfunction "46_46") (pintype "passive"))
      (node (ref "U3B") (pin "14") (pinfunction "4A_14") (pintype "input"))
      (node (ref "U7A") (pin "19") (pinfunction "8Q_19") (pintype "tri_state"))
      (node (ref "U7D") (pin "3") (pinfunction "A7_3") (pintype "input"))
    )
    (net (code "390") (name "IA8") (class "Default")
      (node (ref "CONN5") (pin "44") (pinfunction "44_44") (pintype "passive"))
      (node (ref "U3C") (pin "2") (pinfunction "1A_2") (pintype "input"))
      (node (ref "U7B") (pin "2") (pinfunction "1Q_2") (pintype "tri_state"))
      (node (ref "U7D") (pin "25") (pinfunction "A8_25") (pintype "input"))
      (node (ref "U8A") (pin "64") (pinfunction "MC99_64") (pintype "bidirectional"))
    )
    (net (code "391") (name "IA9") (class "Default")
      (node (ref "CONN5") (pin "42") (pinfunction "42_42") (pintype "passive"))
      (node (ref "U3C") (pin "5") (pinfunction "2A_5") (pintype "input"))
      (node (ref "U7B") (pin "5") (pinfunction "2Q_5") (pintype "tri_state"))
      (node (ref "U7D") (pin "24") (pinfunction "A9_24") (pintype "input"))
      (node (ref "U8A") (pin "65") (pinfunction "MC101_65") (pintype "bidirectional"))
    )
    (net (code "392") (name "IA10") (class "Default")
      (node (ref "CONN5") (pin "40") (pinfunction "40_40") (pintype "passive"))
      (node (ref "U3C") (pin "11") (pinfunction "3A_11") (pintype "input"))
      (node (ref "U7B") (pin "6") (pinfunction "3Q_6") (pintype "tri_state"))
      (node (ref "U7D") (pin "21") (pinfunction "A10_21") (pintype "input"))
      (node (ref "U8A") (pin "63") (pinfunction "MC97_63") (pintype "bidirectional"))
    )
    (net (code "393") (name "IA11") (class "Default")
      (node (ref "CONN5") (pin "38") (pinfunction "38_38") (pintype "passive"))
      (node (ref "U3C") (pin "14") (pinfunction "4A_14") (pintype "input"))
      (node (ref "U7B") (pin "9") (pinfunction "4Q_9") (pintype "tri_state"))
      (node (ref "U7D") (pin "23") (pinfunction "A11_23") (pintype "input"))
      (node (ref "U8A") (pin "61") (pinfunction "MC94_61") (pintype "bidirectional"))
    )
    (net (code "394") (name "IA12") (class "Default")
      (node (ref "CONN5") (pin "36") (pinfunction "36_36") (pintype "passive"))
      (node (ref "U3D") (pin "2") (pinfunction "1A_2") (pintype "input"))
      (node (ref "U7B") (pin "12") (pinfunction "5Q_12") (pintype "tri_state"))
      (node (ref "U7D") (pin "2") (pinfunction "A12_2") (pintype "input"))
    )
    (net (code "395") (name "IA13") (class "Default")
      (node (ref "CONN5") (pin "34") (pinfunction "34_34") (pintype "passive"))
      (node (ref "U3D") (pin "5") (pinfunction "2A_5") (pintype "input"))
      (node (ref "U7B") (pin "15") (pinfunction "6Q_15") (pintype "tri_state"))
      (node (ref "U7D") (pin "26") (pinfunction "A13_26") (pintype "input"))
    )
    (net (code "396") (name "IA14") (class "Default")
      (node (ref "CONN5") (pin "32") (pinfunction "32_32") (pintype "passive"))
      (node (ref "U3D") (pin "11") (pinfunction "3A_11") (pintype "input"))
      (node (ref "U7B") (pin "16") (pinfunction "7Q_16") (pintype "tri_state"))
      (node (ref "U7D") (pin "27") (pinfunction "A14_27") (pintype "input"))
    )
    (net (code "397") (name "IA15") (class "Default")
      (node (ref "CONN5") (pin "30") (pinfunction "30_30") (pintype "passive"))
      (node (ref "U3D") (pin "14") (pinfunction "4A_14") (pintype "input"))
      (node (ref "U7B") (pin "19") (pinfunction "8Q_19") (pintype "tri_state"))
      (node (ref "U7D") (pin "1") (pinfunction "A15_1") (pintype "input"))
    )
    (net (code "398") (name "IA16") (class "Default")
      (node (ref "CONN5") (pin "28") (pinfunction "28_28") (pintype "passive"))
      (node (ref "U7C") (pin "2") (pinfunction "1Q_2") (pintype "tri_state"))
      (node (ref "U8A") (pin "67") (pinfunction "MC104_67") (pintype "bidirectional"))
    )
    (net (code "399") (name "IA17") (class "Default")
      (node (ref "CONN5") (pin "26") (pinfunction "26_26") (pintype "passive"))
      (node (ref "U7C") (pin "5") (pinfunction "2Q_5") (pintype "tri_state"))
      (node (ref "U8A") (pin "68") (pinfunction "MC105_68") (pintype "bidirectional"))
    )
    (net (code "400") (name "IA18") (class "Default")
      (node (ref "CONN5") (pin "24") (pinfunction "24_24") (pintype "passive"))
      (node (ref "U7C") (pin "6") (pinfunction "3Q_6") (pintype "tri_state"))
      (node (ref "U8A") (pin "69") (pinfunction "MC107_69") (pintype "bidirectional"))
    )
    (net (code "401") (name "IA19") (class "Default")
      (node (ref "CONN5") (pin "22") (pinfunction "22_22") (pintype "passive"))
      (node (ref "U7C") (pin "9") (pinfunction "4Q_9") (pintype "tri_state"))
      (node (ref "U8A") (pin "70") (pinfunction "MC109_70") (pintype "bidirectional"))
    )
    (net (code "402") (name "INTR") (class "Default")
      (node (ref "U5A") (pin "18") (pinfunction "INTR_18") (pintype "input"))
      (node (ref "U6C") (pin "17") (pinfunction "INT_17") (pintype "output"))
    )
    (net (code "403") (name "IR0") (class "Default")
      (node (ref "U6C") (pin "18") (pinfunction "IR0_18") (pintype "input"))
      (node (ref "U8A") (pin "80") (pinfunction "MC126_80") (pintype "bidirectional"))
    )
    (net (code "404") (name "IR1") (class "Default")
      (node (ref "U5B") (pin "32") (pinfunction "INT_32") (pintype "output"))
      (node (ref "U6C") (pin "19") (pinfunction "IR1_19") (pintype "input"))
    )
    (net (code "405") (name "IR3") (class "Default")
      (node (ref "CONN3") (pin "3") (pinfunction "3_3") (pintype "passive"))
      (node (ref "CONN5") (pin "47") (pinfunction "47_47") (pintype "passive"))
      (node (ref "U6C") (pin "21") (pinfunction "IR3_21") (pintype "input"))
    )
    (net (code "406") (name "IR4") (class "Default")
      (node (ref "CONN5") (pin "45") (pinfunction "45_45") (pintype "passive"))
      (node (ref "U6C") (pin "22") (pinfunction "IR4_22") (pintype "input"))
    )
    (net (code "407") (name "IR5") (class "Default")
      (node (ref "CONN5") (pin "41") (pinfunction "41_41") (pintype "passive"))
      (node (ref "U6C") (pin "23") (pinfunction "IR5_23") (pintype "input"))
    )
    (net (code "408") (name "IR6") (class "Default")
      (node (ref "CONN5") (pin "39") (pinfunction "39_39") (pintype "passive"))
      (node (ref "U6C") (pin "24") (pinfunction "IR6_24") (pintype "input"))
    )
    (net (code "409") (name "MA0") (class "Default")
      (node (ref "U3A") (pin "4") (pinfunction "1Y_4") (pintype "tri_state"))
      (node (ref "U4A") (pin "12") (pinfunction "A0_12") (pintype "input"))
      (node (ref "U4B") (pin "12") (pinfunction "A0_12") (pintype "input"))
    )
    (net (code "410") (name "MA1") (class "Default")
      (node (ref "U3A") (pin "7") (pinfunction "2Y_7") (pintype "tri_state"))
      (node (ref "U4A") (pin "11") (pinfunction "A1_11") (pintype "input"))
      (node (ref "U4B") (pin "11") (pinfunction "A1_11") (pintype "input"))
    )
    (net (code "411") (name "MA2") (class "Default")
      (node (ref "U3A") (pin "9") (pinfunction "3Y_9") (pintype "tri_state"))
      (node (ref "U4A") (pin "10") (pinfunction "A2_10") (pintype "input"))
      (node (ref "U4B") (pin "10") (pinfunction "A2_10") (pintype "input"))
    )
    (net (code "412") (name "MA3") (class "Default")
      (node (ref "U3A") (pin "12") (pinfunction "4Y_12") (pintype "tri_state"))
      (node (ref "U4A") (pin "9") (pinfunction "A3_9") (pintype "input"))
      (node (ref "U4B") (pin "9") (pinfunction "A3_9") (pintype "input"))
    )
    (net (code "413") (name "MA4") (class "Default")
      (node (ref "U3B") (pin "4") (pinfunction "1Y_4") (pintype "tri_state"))
      (node (ref "U4A") (pin "8") (pinfunction "A4_8") (pintype "input"))
      (node (ref "U4B") (pin "8") (pinfunction "A4_8") (pintype "input"))
    )
    (net (code "414") (name "MA5") (class "Default")
      (node (ref "U3B") (pin "7") (pinfunction "2Y_7") (pintype "tri_state"))
      (node (ref "U4A") (pin "7") (pinfunction "A5_7") (pintype "input"))
      (node (ref "U4B") (pin "7") (pinfunction "A5_7") (pintype "input"))
    )
    (net (code "415") (name "MA6") (class "Default")
      (node (ref "U3B") (pin "9") (pinfunction "3Y_9") (pintype "tri_state"))
      (node (ref "U4A") (pin "6") (pinfunction "A6_6") (pintype "input"))
      (node (ref "U4B") (pin "6") (pinfunction "A6_6") (pintype "input"))
    )
    (net (code "416") (name "MA7") (class "Default")
      (node (ref "U3B") (pin "12") (pinfunction "4Y_12") (pintype "tri_state"))
      (node (ref "U4A") (pin "5") (pinfunction "A7_5") (pintype "input"))
      (node (ref "U4B") (pin "5") (pinfunction "A7_5") (pintype "input"))
    )
    (net (code "417") (name "MA8") (class "Default")
      (node (ref "U3C") (pin "4") (pinfunction "1Y_4") (pintype "tri_state"))
      (node (ref "U4A") (pin "27") (pinfunction "A8_27") (pintype "input"))
      (node (ref "U4B") (pin "27") (pinfunction "A8_27") (pintype "input"))
    )
    (net (code "418") (name "MA9") (class "Default")
      (node (ref "U3C") (pin "7") (pinfunction "2Y_7") (pintype "tri_state"))
      (node (ref "U4A") (pin "26") (pinfunction "A9_26") (pintype "input"))
      (node (ref "U4B") (pin "26") (pinfunction "A9_26") (pintype "input"))
    )
    (net (code "419") (name "MA10") (class "Default")
      (node (ref "U3C") (pin "9") (pinfunction "3Y_9") (pintype "tri_state"))
      (node (ref "U4A") (pin "23") (pinfunction "A10_23") (pintype "input"))
      (node (ref "U4B") (pin "23") (pinfunction "A10_23") (pintype "input"))
    )
    (net (code "420") (name "MA11") (class "Default")
      (node (ref "U3C") (pin "12") (pinfunction "4Y_12") (pintype "tri_state"))
      (node (ref "U4A") (pin "25") (pinfunction "A11_25") (pintype "input"))
      (node (ref "U4B") (pin "25") (pinfunction "A11_25") (pintype "input"))
    )
    (net (code "421") (name "MA12") (class "Default")
      (node (ref "U3D") (pin "4") (pinfunction "1Y_4") (pintype "tri_state"))
      (node (ref "U4A") (pin "4") (pinfunction "A12_4") (pintype "input"))
      (node (ref "U4B") (pin "4") (pinfunction "A12_4") (pintype "input"))
    )
    (net (code "422") (name "MA13") (class "Default")
      (node (ref "U3D") (pin "7") (pinfunction "2Y_7") (pintype "tri_state"))
      (node (ref "U4A") (pin "28") (pinfunction "A13_28") (pintype "input"))
      (node (ref "U4B") (pin "28") (pinfunction "A13_28") (pintype "input"))
    )
    (net (code "423") (name "MA14") (class "Default")
      (node (ref "U3D") (pin "9") (pinfunction "3Y_9") (pintype "tri_state"))
      (node (ref "U4A") (pin "3") (pinfunction "A14_3") (pintype "input"))
      (node (ref "U4B") (pin "3") (pinfunction "A14_3") (pintype "input"))
    )
    (net (code "424") (name "MA15") (class "Default")
      (node (ref "U3D") (pin "12") (pinfunction "4Y_12") (pintype "tri_state"))
      (node (ref "U4A") (pin "31") (pinfunction "A15_31") (pintype "input"))
      (node (ref "U4B") (pin "31") (pinfunction "A15_31") (pintype "input"))
    )
    (net (code "425") (name "MC93") (class "Default")
      (node (ref "CONN5") (pin "27") (pinfunction "27_27") (pintype "passive"))
      (node (ref "U8A") (pin "60") (pinfunction "MC93_60") (pintype "bidirectional"))
    )
    (net (code "426") (name "MD0") (class "Default")
      (node (ref "CONN2") (pin "2") (pinfunction "2_2") (pintype "passive"))
      (node (ref "U4A") (pin "13") (pinfunction "I/O00_13") (pintype "bidirectional"))
      (node (ref "U4B") (pin "13") (pinfunction "I/O00_13") (pintype "bidirectional"))
      (node (ref "U4C") (pin "18") (pinfunction "B1_18") (pintype "bidirectional"))
    )
    (net (code "427") (name "MD1") (class "Default")
      (node (ref "CONN2") (pin "4") (pinfunction "4_4") (pintype "passive"))
      (node (ref "U4A") (pin "14") (pinfunction "I/O01_14") (pintype "bidirectional"))
      (node (ref "U4B") (pin "14") (pinfunction "I/O01_14") (pintype "bidirectional"))
      (node (ref "U4C") (pin "17") (pinfunction "B2_17") (pintype "bidirectional"))
    )
    (net (code "428") (name "MD2") (class "Default")
      (node (ref "CONN2") (pin "6") (pinfunction "6_6") (pintype "passive"))
      (node (ref "U4A") (pin "15") (pinfunction "I/O02_15") (pintype "bidirectional"))
      (node (ref "U4B") (pin "15") (pinfunction "I/O02_15") (pintype "bidirectional"))
      (node (ref "U4C") (pin "16") (pinfunction "B3_16") (pintype "bidirectional"))
    )
    (net (code "429") (name "MD3") (class "Default")
      (node (ref "CONN2") (pin "8") (pinfunction "8_8") (pintype "passive"))
      (node (ref "U4A") (pin "17") (pinfunction "I/O03_17") (pintype "bidirectional"))
      (node (ref "U4B") (pin "17") (pinfunction "I/O03_17") (pintype "bidirectional"))
      (node (ref "U4C") (pin "15") (pinfunction "B4_15") (pintype "bidirectional"))
    )
    (net (code "430") (name "MD4") (class "Default")
      (node (ref "CONN2") (pin "10") (pinfunction "10_10") (pintype "passive"))
      (node (ref "U4A") (pin "18") (pinfunction "I/O04_18") (pintype "bidirectional"))
      (node (ref "U4B") (pin "18") (pinfunction "I/O04_18") (pintype "bidirectional"))
      (node (ref "U4C") (pin "14") (pinfunction "B5_14") (pintype "bidirectional"))
    )
    (net (code "431") (name "MD5") (class "Default")
      (node (ref "CONN2") (pin "12") (pinfunction "12_12") (pintype "passive"))
      (node (ref "U4A") (pin "19") (pinfunction "I/O05_19") (pintype "bidirectional"))
      (node (ref "U4B") (pin "19") (pinfunction "I/O05_19") (pintype "bidirectional"))
      (node (ref "U4C") (pin "13") (pinfunction "B6_13") (pintype "bidirectional"))
    )
    (net (code "432") (name "MD6") (class "Default")
      (node (ref "CONN2") (pin "14") (pinfunction "14_14") (pintype "passive"))
      (node (ref "U4A") (pin "20") (pinfunction "I/O06_20") (pintype "bidirectional"))
      (node (ref "U4B") (pin "20") (pinfunction "I/O06_20") (pintype "bidirectional"))
      (node (ref "U4C") (pin "12") (pinfunction "B7_12") (pintype "bidirectional"))
    )
    (net (code "433") (name "MD7") (class "Default")
      (node (ref "CONN2") (pin "16") (pinfunction "16_16") (pintype "passive"))
      (node (ref "U4A") (pin "21") (pinfunction "I/O07_21") (pintype "bidirectional"))
      (node (ref "U4B") (pin "21") (pinfunction "I/O07_21") (pintype "bidirectional"))
      (node (ref "U4C") (pin "11") (pinfunction "B8_11") (pintype "bidirectional"))
    )
    (net (code "434") (name "MISO") (class "Default")
      (node (ref "CONN3") (pin "2") (pinfunction "2_2") (pintype "passive"))
      (node (ref "CONN5") (pin "31") (pinfunction "31_31") (pintype "passive"))
      (node (ref "J1") (pin "7") (pinfunction "DAT0/DO_7") (pintype "bidirectional"))
      (node (ref "R2") (pin "1") (pinfunction "1_1") (pintype "passive"))
      (node (ref "U8A") (pin "16") (pinfunction "MC27_16") (pintype "bidirectional"))
    )
    (net (code "435") (name "MOSI") (class "Default")
      (node (ref "CONN3") (pin "4") (pinfunction "4_4") (pintype "passive"))
      (node (ref "CONN5") (pin "33") (pinfunction "33_33") (pintype "passive"))
      (node (ref "RN4") (pin "9") (pinfunction "2_9") (pintype "passive"))
      (node (ref "U10A") (pin "3") (pinfunction "I_3") (pintype "input"))
      (node (ref "U8A") (pin "17") (pinfunction "MC25_17") (pintype "bidirectional"))
    )
    (net (code "436") (name "MOSI'") (class "Default")
      (node (ref "J1") (pin "2") (pinfunction "CMD/DI_2") (pintype "bidirectional"))
      (node (ref "U10A") (pin "2") (pinfunction "O_2") (pintype "output"))
    )
    (net (code "437") (name "NMI") (class "Default")
      (node (ref "U5A") (pin "17") (pinfunction "NMI_17") (pintype "input"))
      (node (ref "U8A") (pin "74") (pinfunction "MC117_74") (pintype "bidirectional"))
    )
    (net (code "438") (name "Net-(LED1-C)") (class "Default")
      (node (ref "LED1") (pin "K") (pinfunction "C_K") (pintype "passive"))
      (node (ref "U10A") (pin "10") (pinfunction "O_10") (pintype "output"))
    )
    (net (code "439") (name "Net-(RN1B-2)") (class "Default")
      (node (ref "RN1") (pin "3") (pinfunction "2_3") (pintype "passive"))
      (node (ref "U5A") (pin "26") (pinfunction "S0_26") (pintype "output"))
      (node (ref "U5B") (pin "26") (pinfunction "S0_26") (pintype "bidirectional"))
      (node (ref "U5C") (pin "19") (pinfunction "~{S0}_19") (pintype "input"))
    )
    (net (code "440") (name "Net-(RN1C-2)") (class "Default")
      (node (ref "RN1") (pin "4") (pinfunction "2_4") (pintype "passive"))
      (node (ref "U5A") (pin "27") (pinfunction "S1_27") (pintype "output"))
      (node (ref "U5B") (pin "27") (pinfunction "S1_27") (pintype "bidirectional"))
      (node (ref "U5C") (pin "3") (pinfunction "~{S1}_3") (pintype "input"))
    )
    (net (code "441") (name "Net-(RN1D-2)") (class "Default")
      (node (ref "RN1") (pin "5") (pinfunction "2_5") (pintype "passive"))
      (node (ref "U5A") (pin "28") (pinfunction "S2_28") (pintype "output"))
      (node (ref "U5B") (pin "28") (pinfunction "S2_28") (pintype "bidirectional"))
      (node (ref "U5C") (pin "18") (pinfunction "~{S2}_18") (pintype "input"))
    )
    (net (code "442") (name "Net-(RN1E-2)") (class "Default")
      (node (ref "RN1") (pin "6") (pinfunction "2_6") (pintype "passive"))
      (node (ref "U5A") (pin "30") (pinfunction "RQ/GT1_30") (pintype "bidirectional"))
      (node (ref "U5B") (pin "31") (pinfunction "RQ/GT0_31") (pintype "bidirectional"))
    )
    (net (code "443") (name "Net-(RN1F-2)") (class "Default")
      (node (ref "RN1") (pin "7") (pinfunction "2_7") (pintype "passive"))
      (node (ref "U5A") (pin "31") (pinfunction "RQ/GT0_31") (pintype "bidirectional"))
    )
    (net (code "444") (name "Net-(RN1H-2)") (class "Default")
      (node (ref "RN1") (pin "9") (pinfunction "2_9") (pintype "passive"))
      (node (ref "U5B") (pin "34") (pinfunction "BHE/S7_34") (pintype "bidirectional"))
    )
    (net (code "445") (name "Net-(RN3C-2)") (class "Default")
      (node (ref "RN3") (pin "4") (pinfunction "2_4") (pintype "passive"))
      (node (ref "U6A") (pin "13") (pinfunction "PB3_13") (pintype "bidirectional"))
      (node (ref "U6B") (pin "1") (pinfunction "PA3_1") (pintype "bidirectional"))
    )
    (net (code "446") (name "Net-(RN3D-2)") (class "Default")
      (node (ref "RN3") (pin "5") (pinfunction "2_5") (pintype "passive"))
      (node (ref "U6A") (pin "14") (pinfunction "PB4_14") (pintype "bidirectional"))
      (node (ref "U6B") (pin "40") (pinfunction "PA4_40") (pintype "bidirectional"))
    )
    (net (code "447") (name "Net-(RN3E-2)") (class "Default")
      (node (ref "RN3") (pin "6") (pinfunction "2_6") (pintype "passive"))
      (node (ref "U6A") (pin "15") (pinfunction "PB5_15") (pintype "bidirectional"))
      (node (ref "U6B") (pin "39") (pinfunction "PA5_39") (pintype "bidirectional"))
    )
    (net (code "448") (name "Net-(RN3F-2)") (class "Default")
      (node (ref "RN3") (pin "7") (pinfunction "2_7") (pintype "passive"))
      (node (ref "U6A") (pin "12") (pinfunction "PB2_12") (pintype "bidirectional"))
      (node (ref "U6B") (pin "11") (pinfunction "PC6_11") (pintype "bidirectional"))
    )
    (net (code "449") (name "Net-(RN3H-2)") (class "Default")
      (node (ref "RN3") (pin "9") (pinfunction "2_9") (pintype "passive"))
      (node (ref "U6A") (pin "24") (pinfunction "/FLAG_24") (pintype "input"))
      (node (ref "U6B") (pin "15") (pinfunction "PC1_15") (pintype "bidirectional"))
    )
    (net (code "450") (name "Net-(U5AA-QS0)") (class "Default")
      (node (ref "U5A") (pin "25") (pinfunction "QS0_25") (pintype "output"))
      (node (ref "U5B") (pin "25") (pinfunction "QS0_25") (pintype "input"))
    )
    (net (code "451") (name "Net-(U5AA-QS1)") (class "Default")
      (node (ref "U5A") (pin "24") (pinfunction "QS1_24") (pintype "output"))
      (node (ref "U5B") (pin "24") (pinfunction "QS1_24") (pintype "input"))
    )
    (net (code "452") (name "Net-(U5AA-TEST)") (class "Default")
      (node (ref "RN1") (pin "2") (pinfunction "2_2") (pintype "passive"))
      (node (ref "U5A") (pin "23") (pinfunction "TEST_23") (pintype "input"))
      (node (ref "U5B") (pin "23") (pinfunction "BUSY_23") (pintype "output"))
    )
    (net (code "453") (name "Net-(U6AA-CNT)") (class "Default")
      (node (ref "U6A") (pin "17") (pinfunction "PB7_17") (pintype "bidirectional"))
      (node (ref "U6A") (pin "40") (pinfunction "CNT_40") (pintype "input"))
      (node (ref "U6C") (pin "25") (pinfunction "IR7_25") (pintype "input"))
    )
    (net (code "454") (name "Net-(U6AA-PA0)") (class "Default")
      (node (ref "U6A") (pin "2") (pinfunction "PA0_2") (pintype "bidirectional"))
      (node (ref "U6B") (pin "18") (pinfunction "PB0_18") (pintype "bidirectional"))
    )
    (net (code "455") (name "Net-(U6AA-PA1)") (class "Default")
      (node (ref "U6A") (pin "3") (pinfunction "PA1_3") (pintype "bidirectional"))
      (node (ref "U6B") (pin "19") (pinfunction "PB1_19") (pintype "bidirectional"))
    )
    (net (code "456") (name "Net-(U6AA-PA2)") (class "Default")
      (node (ref "U6A") (pin "4") (pinfunction "PA2_4") (pintype "bidirectional"))
      (node (ref "U6B") (pin "20") (pinfunction "PB2_20") (pintype "bidirectional"))
    )
    (net (code "457") (name "Net-(U6AA-PA3)") (class "Default")
      (node (ref "U6A") (pin "5") (pinfunction "PA3_5") (pintype "bidirectional"))
      (node (ref "U6B") (pin "21") (pinfunction "PB3_21") (pintype "bidirectional"))
    )
    (net (code "458") (name "Net-(U6AA-PA4)") (class "Default")
      (node (ref "U6A") (pin "6") (pinfunction "PA4_6") (pintype "bidirectional"))
      (node (ref "U6B") (pin "22") (pinfunction "PB4_22") (pintype "bidirectional"))
    )
    (net (code "459") (name "Net-(U6AA-PA5)") (class "Default")
      (node (ref "U6A") (pin "7") (pinfunction "PA5_7") (pintype "bidirectional"))
      (node (ref "U6B") (pin "23") (pinfunction "PB5_23") (pintype "bidirectional"))
    )
    (net (code "460") (name "Net-(U6AA-PA6)") (class "Default")
      (node (ref "U6A") (pin "8") (pinfunction "PA6_8") (pintype "bidirectional"))
      (node (ref "U6B") (pin "24") (pinfunction "PB6_24") (pintype "bidirectional"))
    )
    (net (code "461") (name "Net-(U6AA-PA7)") (class "Default")
      (node (ref "U6A") (pin "9") (pinfunction "PA7_9") (pintype "bidirectional"))
      (node (ref "U6B") (pin "25") (pinfunction "PB7_25") (pintype "bidirectional"))
    )
    (net (code "462") (name "Net-(U10AE-O)") (class "Default")
      (node (ref "LED2") (pin "A") (pinfunction "A_A") (pintype "passive"))
      (node (ref "U10A") (pin "12") (pinfunction "O_12") (pintype "output"))
    )
    (net (code "463") (name "Net-(U10B-VBAT)") (class "Default")
      (node (ref "G1") (pin "+") (pinfunction "+_+") (pintype "passive"))
      (node (ref "U10B") (pin "3") (pinfunction "VBAT_3") (pintype "passive"))
    )
    (net (code "464") (name "Net-(U10B-X1)") (class "Default")
      (node (ref "U10B") (pin "1") (pinfunction "X1_1") (pintype "input"))
      (node (ref "XTAL2") (pin "2") (pinfunction "2_2") (pintype "passive"))
    )
    (net (code "465") (name "Net-(U10B-X2)") (class "Default")
      (node (ref "U10B") (pin "2") (pinfunction "X2_2") (pintype "output"))
      (node (ref "XTAL2") (pin "1") (pinfunction "1_1") (pintype "passive"))
    )
    (net (code "466") (name "Net-(U10C-A0)") (class "Default")
      (node (ref "JP1") (pin "2") (pinfunction "2_2") (pintype "passive"))
      (node (ref "R1") (pin "2") (pinfunction "2_2") (pintype "passive"))
      (node (ref "U10C") (pin "1") (pinfunction "A0_1") (pintype "input"))
    )
    (net (code "467") (name "OSC") (class "Default")
      (node (ref "CONN5") (pin "57") (pinfunction "57_57") (pintype "passive"))
      (node (ref "U8A") (pin "2") (pinfunction "OE2/GCLK2/INPUT_2") (pintype "bidirectional"))
      (node (ref "XTAL1") (pin "8") (pinfunction "OUT_8") (pintype "output"))
    )
    (net (code "468") (name "PA1") (class "Default")
      (node (ref "RN3") (pin "3") (pinfunction "2_3") (pintype "passive"))
      (node (ref "U6A") (pin "11") (pinfunction "PB1_11") (pintype "bidirectional"))
      (node (ref "U6B") (pin "3") (pinfunction "PA1_3") (pintype "bidirectional"))
      (node (ref "U8A") (pin "79") (pinfunction "MC125_79") (pintype "bidirectional"))
    )
    (net (code "469") (name "PA2") (class "Default")
      (node (ref "CONN5") (pin "5") (pinfunction "5_5") (pintype "passive"))
      (node (ref "RN4") (pin "5") (pinfunction "2_5") (pintype "passive"))
      (node (ref "U6B") (pin "2") (pinfunction "PA2_2") (pintype "bidirectional"))
    )
    (net (code "470") (name "PA6") (class "Default")
      (node (ref "CONN3") (pin "5") (pinfunction "5_5") (pintype "passive"))
      (node (ref "CONN5") (pin "13") (pinfunction "13_13") (pintype "passive"))
      (node (ref "U6B") (pin "38") (pinfunction "PA6_38") (pintype "bidirectional"))
    )
    (net (code "471") (name "PA7") (class "Default")
      (node (ref "CONN5") (pin "17") (pinfunction "17_17") (pintype "passive"))
      (node (ref "RN4") (pin "2") (pinfunction "2_2") (pintype "passive"))
      (node (ref "U6B") (pin "37") (pinfunction "PA7_37") (pintype "bidirectional"))
    )
    (net (code "472") (name "PC0") (class "Default")
      (node (ref "U10A") (pin "11") (pinfunction "I_11") (pintype "input"))
      (node (ref "U6B") (pin "14") (pinfunction "PC0_14") (pintype "bidirectional"))
    )
    (net (code "473") (name "PC3") (class "Default")
      (node (ref "CONN5") (pin "43") (pinfunction "43_43") (pintype "passive"))
      (node (ref "U6B") (pin "17") (pinfunction "PC3_17") (pintype "bidirectional"))
    )
    (net (code "474") (name "PC4") (class "Default")
      (node (ref "CONN3") (pin "7") (pinfunction "7_7") (pintype "passive"))
      (node (ref "CONN5") (pin "9") (pinfunction "9_9") (pintype "passive"))
      (node (ref "U6B") (pin "13") (pinfunction "PC4_13") (pintype "bidirectional"))
    )
    (net (code "475") (name "PC5") (class "Default")
      (node (ref "RN3") (pin "8") (pinfunction "2_8") (pintype "passive"))
      (node (ref "U6B") (pin "12") (pinfunction "PC5_12") (pintype "bidirectional"))
      (node (ref "U8A") (pin "4") (pinfunction "MC16_4") (pintype "bidirectional"))
    )
    (net (code "476") (name "PC7") (class "Default")
      (node (ref "CONN5") (pin "7") (pinfunction "7_7") (pintype "passive"))
      (node (ref "U10A") (pin "7") (pinfunction "I_7") (pintype "input"))
      (node (ref "U6B") (pin "10") (pinfunction "PC7_10") (pintype "bidirectional"))
    )
    (net (code "477") (name "PHI2") (class "Default")
      (node (ref "CONN1") (pin "25") (pinfunction "25_25") (pintype "passive"))
      (node (ref "U6A") (pin "25") (pinfunction "PHI2_25") (pintype "input"))
    )
    (net (code "478") (name "READY") (class "Default")
      (node (ref "U5A") (pin "22") (pinfunction "READY_22") (pintype "input"))
      (node (ref "U5B") (pin "22") (pinfunction "READY_22") (pintype "input"))
      (node (ref "U8A") (pin "58") (pinfunction "MC91_58") (pintype "bidirectional"))
    )
    (net (code "479") (name "RESET") (class "Default")
      (node (ref "CONN5") (pin "1") (pinfunction "1_1") (pintype "passive"))
      (node (ref "U5A") (pin "21") (pinfunction "RESET_21") (pintype "input"))
      (node (ref "U5B") (pin "21") (pinfunction "RESET_21") (pintype "input"))
      (node (ref "U6B") (pin "35") (pinfunction "RESET_35") (pintype "input"))
      (node (ref "U8A") (pin "12") (pinfunction "PD1/MC3_12") (pintype "bidirectional"))
    )
    (net (code "480") (name "R{slash}W") (class "Default")
      (node (ref "CONN1") (pin "19") (pinfunction "19_19") (pintype "passive"))
      (node (ref "U2A") (pin "27") (pinfunction "~{WE}_27") (pintype "input"))
      (node (ref "U2B") (pin "27") (pinfunction "~{WE}_27") (pintype "input"))
      (node (ref "U2C") (pin "27") (pinfunction "~{WE}_27") (pintype "input"))
      (node (ref "U2D") (pin "27") (pinfunction "~{WE}_27") (pintype "input"))
      (node (ref "U2E") (pin "21") (pinfunction "~{WE}_21") (pintype "input"))
      (node (ref "U6A") (pin "22") (pinfunction "R/W_22") (pintype "input"))
      (node (ref "U8A") (pin "54") (pinfunction "MC83_54") (pintype "bidirectional"))
    )
    (net (code "481") (name "SCK") (class "Default")
      (node (ref "CONN3") (pin "6") (pinfunction "6_6") (pintype "passive"))
      (node (ref "CONN5") (pin "29") (pinfunction "29_29") (pintype "passive"))
      (node (ref "RN4") (pin "8") (pinfunction "2_8") (pintype "passive"))
      (node (ref "U10A") (pin "5") (pinfunction "I_5") (pintype "input"))
      (node (ref "U8A") (pin "18") (pinfunction "MC24_18") (pintype "bidirectional"))
    )
    (net (code "482") (name "SCK'") (class "Default")
      (node (ref "J1") (pin "5") (pinfunction "CLK/SCLK_5") (pintype "bidirectional"))
      (node (ref "U10A") (pin "4") (pinfunction "O_4") (pintype "output"))
    )
    (net (code "483") (name "SCL") (class "Default")
      (node (ref "C10D") (pin "1") (pinfunction "1_1") (pintype "passive"))
      (node (ref "CONN3") (pin "10") (pinfunction "10_10") (pintype "passive"))
      (node (ref "CONN5") (pin "51") (pinfunction "51_51") (pintype "passive"))
      (node (ref "RN4") (pin "6") (pinfunction "2_6") (pintype "passive"))
      (node (ref "U10B") (pin "6") (pinfunction "SCL_6") (pintype "input"))
      (node (ref "U10C") (pin "6") (pinfunction "SCL_6") (pintype "input"))
      (node (ref "U8A") (pin "21") (pinfunction "MC19_21") (pintype "bidirectional"))
    )
    (net (code "484") (name "SDA") (class "Default")
      (node (ref "CONN3") (pin "8") (pinfunction "8_8") (pintype "passive"))
      (node (ref "CONN5") (pin "49") (pinfunction "49_49") (pintype "passive"))
      (node (ref "RN4") (pin "7") (pinfunction "2_7") (pintype "passive"))
      (node (ref "U10B") (pin "5") (pinfunction "SDA_5") (pintype "bidirectional"))
      (node (ref "U10C") (pin "5") (pinfunction "SDA_5") (pintype "bidirectional"))
      (node (ref "U8A") (pin "20") (pinfunction "MC21_20") (pintype "bidirectional"))
    )
    (net (code "485") (name "SP{slash}EN") (class "Default")
      (node (ref "RN1") (pin "8") (pinfunction "2_8") (pintype "passive"))
      (node (ref "U6C") (pin "16") (pinfunction "SP/EN_16") (pintype "bidirectional"))
      (node (ref "U8A") (pin "9") (pinfunction "MC8_9") (pintype "bidirectional"))
    )
    (net (code "486") (name "SQW") (class "Default")
      (node (ref "CONN5") (pin "35") (pinfunction "35_35") (pintype "passive"))
      (node (ref "RN4") (pin "3") (pinfunction "2_3") (pintype "passive"))
      (node (ref "U10B") (pin "7") (pinfunction "SQW_7") (pintype "open_collector"))
    )
    (net (code "487") (name "TCK") (class "Default")
      (node (ref "CONN4") (pin "10") (pinfunction "10_10") (pintype "passive"))
      (node (ref "U8A") (pin "62") (pinfunction "TCK_62") (pintype "bidirectional"))
    )
    (net (code "488") (name "TDI") (class "Default")
      (node (ref "CONN4") (pin "2") (pinfunction "2_2") (pintype "passive"))
      (node (ref "U8A") (pin "14") (pinfunction "TDI_14") (pintype "bidirectional"))
    )
    (net (code "489") (name "TDO") (class "Default")
      (node (ref "CONN4") (pin "8") (pinfunction "8_8") (pintype "passive"))
      (node (ref "U8A") (pin "71") (pinfunction "TDO_71") (pintype "bidirectional"))
    )
    (net (code "490") (name "TMS") (class "Default")
      (node (ref "CONN4") (pin "6") (pinfunction "6_6") (pintype "passive"))
      (node (ref "U8A") (pin "23") (pinfunction "TMS_23") (pintype "bidirectional"))
    )
    (net (code "491") (name "TODCLK") (class "Default")
      (node (ref "CONN1") (pin "21") (pinfunction "21_21") (pintype "passive"))
      (node (ref "U6A") (pin "19") (pinfunction "TOD_19") (pintype "bidirectional"))
      (node (ref "U6C") (pin "20") (pinfunction "IR2_20") (pintype "input"))
    )
    (net (code "492") (name "VCC") (class "Default")
      (node (ref "C10B") (pin "1") (pinfunction "1_1") (pintype "passive"))
      (node (ref "C10C") (pin "1") (pinfunction "1_1") (pintype "passive"))
      (node (ref "C2A") (pin "1") (pinfunction "1_1") (pintype "passive"))
      (node (ref "C2B") (pin "1") (pinfunction "1_1") (pintype "passive"))
      (node (ref "C2C") (pin "1") (pinfunction "1_1") (pintype "passive"))
      (node (ref "C2D") (pin "1") (pinfunction "1_1") (pintype "passive"))
      (node (ref "C2E") (pin "1") (pinfunction "1_1") (pintype "passive"))
      (node (ref "C3A") (pin "1") (pinfunction "1_1") (pintype "passive"))
      (node (ref "C3B") (pin "1") (pinfunction "1_1") (pintype "passive"))
      (node (ref "C3C") (pin "1") (pinfunction "1_1") (pintype "passive"))
      (node (ref "C3D") (pin "1") (pinfunction "1_1") (pintype "passive"))
      (node (ref "C4A") (pin "1") (pinfunction "1_1") (pintype "passive"))
      (node (ref "C4B") (pin "1") (pinfunction "1_1") (pintype "passive"))
      (node (ref "C4C") (pin "1") (pinfunction "1_1") (pintype "passive"))
      (node (ref "C5A") (pin "1") (pinfunction "1_1") (pintype "passive"))
      (node (ref "C5B") (pin "1") (pinfunction "1_1") (pintype "passive"))
      (node (ref "C5C") (pin "1") (pinfunction "1_1") (pintype "passive"))
      (node (ref "C6A") (pin "1") (pinfunction "1_1") (pintype "passive"))
      (node (ref "C6B") (pin "1") (pinfunction "1_1") (pintype "passive"))
      (node (ref "C6C") (pin "1") (pinfunction "1_1") (pintype "passive"))
      (node (ref "C7A") (pin "1") (pinfunction "1_1") (pintype "passive"))
      (node (ref "C7B") (pin "1") (pinfunction "1_1") (pintype "passive"))
      (node (ref "C7C") (pin "1") (pinfunction "1_1") (pintype "passive"))
      (node (ref "C7D") (pin "1") (pinfunction "1_1") (pintype "passive"))
      (node (ref "C8A") (pin "+") (pinfunction "+_+") (pintype "passive"))
      (node (ref "CONN1") (pin "1") (pinfunction "1_1") (pintype "passive"))
      (node (ref "CONN1") (pin "2") (pinfunction "2_2") (pintype "passive"))
      (node (ref "CONN1") (pin "3") (pinfunction "3_3") (pintype "passive"))
      (node (ref "CONN1") (pin "4") (pinfunction "4_4") (pintype "passive"))
      (node (ref "CONN2") (pin "38") (pinfunction "38_38") (pintype "passive"))
      (node (ref "CONN2") (pin "40") (pinfunction "40_40") (pintype "passive"))
      (node (ref "CONN3") (pin "1") (pinfunction "1_1") (pintype "passive"))
      (node (ref "CONN4") (pin "7") (pinfunction "7_7") (pintype "passive"))
      (node (ref "CONN5") (pin "3") (pinfunction "3_3") (pintype "passive"))
      (node (ref "IC1") (pin "3") (pinfunction "I_3") (pintype "input"))
      (node (ref "JP1") (pin "1") (pinfunction "1_1") (pintype "passive"))
      (node (ref "RN1") (pin "1") (pinfunction "1_1") (pintype "passive"))
      (node (ref "RN2") (pin "1") (pinfunction "1_1") (pintype "passive"))
      (node (ref "RN3") (pin "1") (pinfunction "1_1") (pintype "passive"))
      (node (ref "RN4") (pin "1") (pinfunction "1_1") (pintype "passive"))
      (node (ref "U10B") (pin "8") (pinfunction "VCC_8") (pintype "power_in"))
      (node (ref "U10C") (pin "8") (pinfunction "VCC_8") (pintype "power_in"))
      (node (ref "U2A") (pin "26") (pinfunction "CS2_26") (pintype "input"))
      (node (ref "U2A") (pin "28") (pinfunction "VCC_28") (pintype "power_in"))
      (node (ref "U2B") (pin "26") (pinfunction "CS2_26") (pintype "input"))
      (node (ref "U2B") (pin "28") (pinfunction "VCC_28") (pintype "power_in"))
      (node (ref "U2C") (pin "26") (pinfunction "CS2_26") (pintype "input"))
      (node (ref "U2C") (pin "28") (pinfunction "VCC_28") (pintype "power_in"))
      (node (ref "U2D") (pin "26") (pinfunction "CS2_26") (pintype "input"))
      (node (ref "U2D") (pin "28") (pinfunction "VCC_28") (pintype "power_in"))
      (node (ref "U4A") (pin "32") (pinfunction "VCC_32") (pintype "power_in"))
      (node (ref "U4B") (pin "32") (pinfunction "VCC_32") (pintype "power_in"))
      (node (ref "U5B") (pin "33") (pinfunction "RQ/GT1_33") (pintype "bidirectional"))
      (node (ref "U5C") (pin "1") (pinfunction "IOB_1") (pintype "input"))
      (node (ref "U5C") (pin "15") (pinfunction "CEN_15") (pintype "input"))
      (node (ref "U8A") (pin "13") (pinfunction "VCCIO_13") (pintype "bidirectional"))
      (node (ref "U8A") (pin "26") (pinfunction "VCCIO_26") (pintype "bidirectional"))
      (node (ref "U8A") (pin "3") (pinfunction "VCCINT_3") (pintype "bidirectional"))
      (node (ref "U8A") (pin "38") (pinfunction "VCCIO_38") (pintype "bidirectional"))
      (node (ref "U8A") (pin "43") (pinfunction "VCCINT_43") (pintype "bidirectional"))
      (node (ref "U8A") (pin "53") (pinfunction "VCCIO_53") (pintype "bidirectional"))
      (node (ref "U8A") (pin "66") (pinfunction "VCCIO_66") (pintype "bidirectional"))
      (node (ref "U8A") (pin "78") (pinfunction "VCCIO_78") (pintype "bidirectional"))
      (node (ref "XTAL1") (pin "14") (pinfunction "VDD_14") (pintype "power_in"))
    )
    (net (code "493") (name "unconnected-(CONN1-Pad11)") (class "Default")
      (node (ref "CONN1") (pin "11") (pinfunction "11_11") (pintype "passive"))
    )
    (net (code "494") (name "unconnected-(CONN1-Pad14)") (class "Default")
      (node (ref "CONN1") (pin "14") (pinfunction "14_14") (pintype "passive"))
    )
    (net (code "495") (name "unconnected-(CONN1-Pad18)") (class "Default")
      (node (ref "CONN1") (pin "18") (pinfunction "18_18") (pintype "passive"))
    )
    (net (code "496") (name "unconnected-(CONN1-Pad22)") (class "Default")
      (node (ref "CONN1") (pin "22") (pinfunction "22_22") (pintype "passive"))
    )
    (net (code "497") (name "unconnected-(CONN1-Pad23)") (class "Default")
      (node (ref "CONN1") (pin "23") (pinfunction "23_23") (pintype "passive"))
    )
    (net (code "498") (name "unconnected-(CONN1-Pad24)") (class "Default")
      (node (ref "CONN1") (pin "24") (pinfunction "24_24") (pintype "passive"))
    )
    (net (code "499") (name "unconnected-(CONN1-Pad27)") (class "Default")
      (node (ref "CONN1") (pin "27") (pinfunction "27_27") (pintype "passive"))
    )
    (net (code "500") (name "unconnected-(CONN1-Pad28)") (class "Default")
      (node (ref "CONN1") (pin "28") (pinfunction "28_28") (pintype "passive"))
    )
    (net (code "501") (name "unconnected-(CONN1-Pad57)") (class "Default")
      (node (ref "CONN1") (pin "57") (pinfunction "57_57") (pintype "passive"))
    )
    (net (code "502") (name "unconnected-(CONN1-Pad59)") (class "Default")
      (node (ref "CONN1") (pin "59") (pinfunction "59_59") (pintype "passive"))
    )
    (net (code "503") (name "unconnected-(CONN1-Pad60)") (class "Default")
      (node (ref "CONN1") (pin "60") (pinfunction "60_60") (pintype "passive"))
    )
    (net (code "504") (name "unconnected-(CONN2-Pad1)") (class "Default")
      (node (ref "CONN2") (pin "1") (pinfunction "1_1") (pintype "passive"))
    )
    (net (code "505") (name "unconnected-(CONN2-Pad3)") (class "Default")
      (node (ref "CONN2") (pin "3") (pinfunction "3_3") (pintype "passive"))
    )
    (net (code "506") (name "unconnected-(CONN2-Pad5)") (class "Default")
      (node (ref "CONN2") (pin "5") (pinfunction "5_5") (pintype "passive"))
    )
    (net (code "507") (name "unconnected-(CONN2-Pad7)") (class "Default")
      (node (ref "CONN2") (pin "7") (pinfunction "7_7") (pintype "passive"))
    )
    (net (code "508") (name "unconnected-(CONN2-Pad9)") (class "Default")
      (node (ref "CONN2") (pin "9") (pinfunction "9_9") (pintype "passive"))
    )
    (net (code "509") (name "unconnected-(CONN2-Pad11)") (class "Default")
      (node (ref "CONN2") (pin "11") (pinfunction "11_11") (pintype "passive"))
    )
    (net (code "510") (name "unconnected-(CONN2-Pad13)") (class "Default")
      (node (ref "CONN2") (pin "13") (pinfunction "13_13") (pintype "passive"))
    )
    (net (code "511") (name "unconnected-(CONN2-Pad15)") (class "Default")
      (node (ref "CONN2") (pin "15") (pinfunction "15_15") (pintype "passive"))
    )
    (net (code "512") (name "unconnected-(CONN2-Pad24)") (class "Default")
      (node (ref "CONN2") (pin "24") (pinfunction "24_24") (pintype "passive"))
    )
    (net (code "513") (name "unconnected-(CONN2-Pad28)") (class "Default")
      (node (ref "CONN2") (pin "28") (pinfunction "28_28") (pintype "passive"))
    )
    (net (code "514") (name "unconnected-(CONN2-Pad30)") (class "Default")
      (node (ref "CONN2") (pin "30") (pinfunction "30_30") (pintype "passive"))
    )
    (net (code "515") (name "unconnected-(CONN2-Pad32)") (class "Default")
      (node (ref "CONN2") (pin "32") (pinfunction "32_32") (pintype "passive"))
    )
    (net (code "516") (name "unconnected-(CONN2-Pad33)") (class "Default")
      (node (ref "CONN2") (pin "33") (pinfunction "33_33") (pintype "passive"))
    )
    (net (code "517") (name "unconnected-(CONN2-Pad34)") (class "Default")
      (node (ref "CONN2") (pin "34") (pinfunction "34_34") (pintype "passive"))
    )
    (net (code "518") (name "unconnected-(CONN2-Pad35)") (class "Default")
      (node (ref "CONN2") (pin "35") (pinfunction "35_35") (pintype "passive"))
    )
    (net (code "519") (name "unconnected-(CONN2-Pad37)") (class "Default")
      (node (ref "CONN2") (pin "37") (pinfunction "37_37") (pintype "passive"))
    )
    (net (code "520") (name "unconnected-(CONN2-Pad39)") (class "Default")
      (node (ref "CONN2") (pin "39") (pinfunction "39_39") (pintype "passive"))
    )
    (net (code "521") (name "unconnected-(CONN4-Pad3)") (class "Default")
      (node (ref "CONN4") (pin "3") (pinfunction "3_3") (pintype "passive"))
    )
    (net (code "522") (name "unconnected-(CONN4-Pad4)") (class "Default")
      (node (ref "CONN4") (pin "4") (pinfunction "4_4") (pintype "passive"))
    )
    (net (code "523") (name "unconnected-(CONN4-Pad5)") (class "Default")
      (node (ref "CONN4") (pin "5") (pinfunction "5_5") (pintype "passive"))
    )
    (net (code "524") (name "unconnected-(G1-+-Pad+@1)") (class "Default")
      (node (ref "G1") (pin "+@1") (pinfunction "+_+@1") (pintype "passive"))
    )
    (net (code "525") (name "unconnected-(J1-CDI#-Pad10)") (class "Default")
      (node (ref "J1") (pin "10") (pinfunction "CDI#_10") (pintype "output"))
    )
    (net (code "526") (name "unconnected-(J1-DAT1-Pad8)") (class "Default")
      (node (ref "J1") (pin "8") (pinfunction "DAT1_8") (pintype "bidirectional"))
    )
    (net (code "527") (name "unconnected-(J1-DAT2-Pad9)") (class "Default")
      (node (ref "J1") (pin "9") (pinfunction "DAT2_9") (pintype "bidirectional"))
    )
    (net (code "528") (name "unconnected-(J1-WP-Pad11)") (class "Default")
      (node (ref "J1") (pin "11") (pinfunction "WP_11") (pintype "output"))
    )
    (net (code "529") (name "unconnected-(U2A-NC-Pad1)") (class "Default")
      (node (ref "U2A") (pin "1") (pinfunction "NC_1") (pintype "no_connect"))
    )
    (net (code "530") (name "unconnected-(U2B-NC-Pad1)") (class "Default")
      (node (ref "U2B") (pin "1") (pinfunction "NC_1") (pintype "no_connect"))
    )
    (net (code "531") (name "unconnected-(U2C-NC-Pad1)") (class "Default")
      (node (ref "U2C") (pin "1") (pinfunction "NC_1") (pintype "no_connect"))
    )
    (net (code "532") (name "unconnected-(U2D-NC-Pad1)") (class "Default")
      (node (ref "U2D") (pin "1") (pinfunction "NC_1") (pintype "no_connect"))
    )
    (net (code "533") (name "unconnected-(U5AA-HIGH-Pad34)") (class "Default")
      (node (ref "U5A") (pin "34") (pinfunction "HIGH_34") (pintype "output"))
    )
    (net (code "534") (name "unconnected-(U5AA-~{LOCK}-Pad29)") (class "Default")
      (node (ref "U5A") (pin "29") (pinfunction "~{LOCK}_29") (pintype "output"))
    )
    (net (code "535") (name "unconnected-(U5AA-~{RD}-Pad32)") (class "Default")
      (node (ref "U5A") (pin "32") (pinfunction "~{RD}_32") (pintype "output"))
    )
    (net (code "536") (name "unconnected-(U5CA-MCE{slash}~{PDEN}-Pad17)") (class "Default")
      (node (ref "U5C") (pin "17") (pinfunction "MCE/~{PDEN}_17") (pintype "output"))
    )
    (net (code "537") (name "unconnected-(U6AA-SP-Pad39)") (class "Default")
      (node (ref "U6A") (pin "39") (pinfunction "SP_39") (pintype "bidirectional"))
    )
    (net (code "538") (name "unconnected-(U6AA-{slash}PC-Pad18)") (class "Default")
      (node (ref "U6A") (pin "18") (pinfunction "/PC_18") (pintype "bidirectional"))
    )
    (net (code "539") (name "unconnected-(U6CA-CAS0-Pad12)") (class "Default")
      (node (ref "U6C") (pin "12") (pinfunction "CAS0_12") (pintype "bidirectional"))
    )
    (net (code "540") (name "unconnected-(U6CA-CAS1-Pad13)") (class "Default")
      (node (ref "U6C") (pin "13") (pinfunction "CAS1_13") (pintype "bidirectional"))
    )
    (net (code "541") (name "unconnected-(U6CA-CAS2-Pad15)") (class "Default")
      (node (ref "U6C") (pin "15") (pinfunction "CAS2_15") (pintype "bidirectional"))
    )
    (net (code "542") (name "unconnected-(U7CA-5D-Pad13)") (class "Default")
      (node (ref "U7C") (pin "13") (pinfunction "5D_13") (pintype "input"))
    )
    (net (code "543") (name "unconnected-(U7CA-5Q-Pad12)") (class "Default")
      (node (ref "U7C") (pin "12") (pinfunction "5Q_12") (pintype "tri_state"))
    )
    (net (code "544") (name "unconnected-(U7CA-6D-Pad14)") (class "Default")
      (node (ref "U7C") (pin "14") (pinfunction "6D_14") (pintype "input"))
    )
    (net (code "545") (name "unconnected-(U7CA-6Q-Pad15)") (class "Default")
      (node (ref "U7C") (pin "15") (pinfunction "6Q_15") (pintype "tri_state"))
    )
    (net (code "546") (name "unconnected-(U7CA-7D-Pad17)") (class "Default")
      (node (ref "U7C") (pin "17") (pinfunction "7D_17") (pintype "input"))
    )
    (net (code "547") (name "unconnected-(U7CA-7Q-Pad16)") (class "Default")
      (node (ref "U7C") (pin "16") (pinfunction "7Q_16") (pintype "tri_state"))
    )
    (net (code "548") (name "unconnected-(U7CA-8D-Pad18)") (class "Default")
      (node (ref "U7C") (pin "18") (pinfunction "8D_18") (pintype "input"))
    )
    (net (code "549") (name "unconnected-(U7CA-8Q-Pad19)") (class "Default")
      (node (ref "U7C") (pin "19") (pinfunction "8Q_19") (pintype "tri_state"))
    )
    (net (code "550") (name "unconnected-(XTAL1-CON-Pad1)") (class "Default")
      (node (ref "XTAL1") (pin "1") (pinfunction "CON_1") (pintype "input"))
    )
    (net (code "551") (name "{slash}AIOWC") (class "Default")
      (node (ref "CONN5") (pin "23") (pinfunction "23_23") (pintype "passive"))
      (node (ref "RN2") (pin "9") (pinfunction "2_9") (pintype "passive"))
      (node (ref "U5C") (pin "12") (pinfunction "~{AIOWC}_12") (pintype "output"))
    )
    (net (code "552") (name "{slash}AMWC") (class "Default")
      (node (ref "CONN5") (pin "19") (pinfunction "19_19") (pintype "passive"))
      (node (ref "U5C") (pin "8") (pinfunction "~{AMWC}_8") (pintype "output"))
    )
    (net (code "553") (name "{slash}BUSY1") (class "Default")
      (node (ref "CONN2") (pin "22") (pinfunction "22_22") (pintype "passive"))
      (node (ref "RN3") (pin "2") (pinfunction "2_2") (pintype "passive"))
      (node (ref "U6A") (pin "10") (pinfunction "PB0_10") (pintype "bidirectional"))
      (node (ref "U6B") (pin "4") (pinfunction "PA0_4") (pintype "bidirectional"))
      (node (ref "U8A") (pin "10") (pinfunction "MC6_10") (pintype "bidirectional"))
    )
    (net (code "554") (name "{slash}BUSY2") (class "Default")
      (node (ref "CONN2") (pin "36") (pinfunction "36_36") (pintype "passive"))
      (node (ref "U10A") (pin "9") (pinfunction "I_9") (pintype "input"))
      (node (ref "U3A") (pin "1") (pinfunction "~{A}/B_1") (pintype "input"))
      (node (ref "U3B") (pin "1") (pinfunction "~{A}/B_1") (pintype "input"))
      (node (ref "U3C") (pin "1") (pinfunction "~{A}/B_1") (pintype "input"))
      (node (ref "U3D") (pin "1") (pinfunction "~{A}/B_1") (pintype "input"))
      (node (ref "U8A") (pin "55") (pinfunction "MC85_55") (pintype "bidirectional"))
    )
    (net (code "555") (name "{slash}CAS") (class "Default")
      (node (ref "CONN1") (pin "26") (pinfunction "26_26") (pintype "passive"))
      (node (ref "CONN2") (pin "26") (pinfunction "26_26") (pintype "passive"))
      (node (ref "U8A") (pin "45") (pinfunction "PD2/MC67_45") (pintype "bidirectional"))
    )
    (net (code "556") (name "{slash}CS_8255") (class "Default")
      (node (ref "U6B") (pin "6") (pinfunction "CS_6") (pintype "input"))
      (node (ref "U8A") (pin "76") (pinfunction "MC120_76") (pintype "bidirectional"))
    )
    (net (code "557") (name "{slash}CS_8259") (class "Default")
      (node (ref "U6C") (pin "1") (pinfunction "CS_1") (pintype "input"))
      (node (ref "U8A") (pin "77") (pinfunction "MC123_77") (pintype "bidirectional"))
    )
    (net (code "558") (name "{slash}EPROM") (class "Default")
      (node (ref "U7D") (pin "20") (pinfunction "~{CE}_20") (pintype "input"))
      (node (ref "U7D") (pin "22") (pinfunction "~{OE}_22") (pintype "input"))
      (node (ref "U8A") (pin "11") (pinfunction "MC5_11") (pintype "bidirectional"))
    )
    (net (code "559") (name "{slash}EPROM1") (class "Default")
      (node (ref "U2A") (pin "20") (pinfunction "~{CS1}_20") (pintype "input"))
      (node (ref "U8A") (pin "49") (pinfunction "MC73_49") (pintype "bidirectional"))
    )
    (net (code "560") (name "{slash}EPROM2") (class "Default")
      (node (ref "U2B") (pin "20") (pinfunction "~{CS1}_20") (pintype "input"))
      (node (ref "U8A") (pin "50") (pinfunction "MC75_50") (pintype "bidirectional"))
    )
    (net (code "561") (name "{slash}EPROM3") (class "Default")
      (node (ref "U2C") (pin "20") (pinfunction "~{CS1}_20") (pintype "input"))
      (node (ref "U8A") (pin "51") (pinfunction "MC77_51") (pintype "bidirectional"))
    )
    (net (code "562") (name "{slash}EPROM4") (class "Default")
      (node (ref "U2D") (pin "20") (pinfunction "~{CS1}_20") (pintype "input"))
      (node (ref "U8A") (pin "52") (pinfunction "MC80_52") (pintype "bidirectional"))
    )
    (net (code "563") (name "{slash}EXTBUFCS") (class "Default")
      (node (ref "CONN1") (pin "20") (pinfunction "20_20") (pintype "passive"))
      (node (ref "U2E") (pin "18") (pinfunction "~{CE}_18") (pintype "input"))
    )
    (net (code "564") (name "{slash}EXTPRTCS") (class "Default")
      (node (ref "CONN1") (pin "30") (pinfunction "30_30") (pintype "passive"))
      (node (ref "U6A") (pin "23") (pinfunction "/CS_23") (pintype "input"))
    )
    (net (code "565") (name "{slash}G") (class "Default")
      (node (ref "U4C") (pin "19") (pinfunction "G_19") (pintype "input"))
      (node (ref "U8A") (pin "15") (pinfunction "MC29_15") (pintype "bidirectional"))
    )
    (net (code "566") (name "{slash}INT0") (class "Default")
      (node (ref "U6A") (pin "16") (pinfunction "PB6_16") (pintype "bidirectional"))
      (node (ref "U8A") (pin "5") (pinfunction "MC14_5") (pintype "bidirectional"))
    )
    (net (code "567") (name "{slash}INTA") (class "Default")
      (node (ref "RN2") (pin "5") (pinfunction "2_5") (pintype "passive"))
      (node (ref "U5C") (pin "14") (pinfunction "~{INTA}_14") (pintype "output"))
      (node (ref "U6C") (pin "26") (pinfunction "INTA_26") (pintype "input"))
    )
    (net (code "568") (name "{slash}IORC") (class "Default")
      (node (ref "CONN5") (pin "25") (pinfunction "25_25") (pintype "passive"))
      (node (ref "RN2") (pin "7") (pinfunction "2_7") (pintype "passive"))
      (node (ref "U5C") (pin "13") (pinfunction "~{IORC}_13") (pintype "output"))
      (node (ref "U6B") (pin "5") (pinfunction "RD_5") (pintype "input"))
      (node (ref "U6C") (pin "3") (pinfunction "RD_3") (pintype "input"))
      (node (ref "U8A") (pin "83") (pinfunction "GCLK1/INPUT_83") (pintype "bidirectional"))
    )
    (net (code "569") (name "{slash}IORDY") (class "Default")
      (node (ref "CONN5") (pin "18") (pinfunction "18_18") (pintype "passive"))
      (node (ref "RN4") (pin "4") (pinfunction "2_4") (pintype "passive"))
      (node (ref "U8A") (pin "44") (pinfunction "MC65_44") (pintype "bidirectional"))
    )
    (net (code "570") (name "{slash}IOWC") (class "Default")
      (node (ref "CONN5") (pin "55") (pinfunction "55_55") (pintype "passive"))
      (node (ref "U5C") (pin "11") (pinfunction "~{IOWC}_11") (pintype "output"))
      (node (ref "U6B") (pin "36") (pinfunction "WR_36") (pintype "input"))
      (node (ref "U6C") (pin "2") (pinfunction "WR_2") (pintype "input"))
      (node (ref "U8A") (pin "84") (pinfunction "OE1/INPUT_84") (pintype "bidirectional"))
    )
    (net (code "571") (name "{slash}IRQ3") (class "Default")
      (node (ref "CONN1") (pin "12") (pinfunction "12_12") (pintype "passive"))
      (node (ref "U6A") (pin "21") (pinfunction "/IRQ_21") (pintype "open_collector"))
    )
    (net (code "572") (name "{slash}MRDC") (class "Default")
      (node (ref "CONN5") (pin "21") (pinfunction "21_21") (pintype "passive"))
      (node (ref "RN2") (pin "6") (pinfunction "2_6") (pintype "passive"))
      (node (ref "U5C") (pin "7") (pinfunction "~{MRDC}_7") (pintype "output"))
      (node (ref "U8A") (pin "6") (pinfunction "MC13_6") (pintype "bidirectional"))
    )
    (net (code "573") (name "{slash}MWTC") (class "Default")
      (node (ref "CONN5") (pin "20") (pinfunction "20_20") (pintype "passive"))
      (node (ref "RN2") (pin "8") (pinfunction "2_8") (pintype "passive"))
      (node (ref "U5C") (pin "9") (pinfunction "~{MWTC}_9") (pintype "output"))
      (node (ref "U8A") (pin "8") (pinfunction "MC11_8") (pintype "bidirectional"))
    )
    (net (code "574") (name "{slash}OE") (class "Default")
      (node (ref "U4A") (pin "24") (pinfunction "OE_24") (pintype "input"))
      (node (ref "U4B") (pin "24") (pinfunction "OE_24") (pintype "input"))
      (node (ref "U8A") (pin "56") (pinfunction "MC86_56") (pintype "bidirectional"))
    )
    (net (code "575") (name "{slash}RAM1") (class "Default")
      (node (ref "U4A") (pin "22") (pinfunction "CE_22") (pintype "input"))
      (node (ref "U8A") (pin "46") (pinfunction "MC69_46") (pintype "bidirectional"))
    )
    (net (code "576") (name "{slash}RAM2") (class "Default")
      (node (ref "U4B") (pin "22") (pinfunction "CE_22") (pintype "input"))
      (node (ref "U8A") (pin "48") (pinfunction "MC72_48") (pintype "bidirectional"))
    )
    (net (code "577") (name "{slash}RESET") (class "Default")
      (node (ref "CONN1") (pin "17") (pinfunction "17_17") (pintype "passive"))
      (node (ref "U6A") (pin "34") (pinfunction "/RES_34") (pintype "input"))
      (node (ref "U8A") (pin "1") (pinfunction "GCLR/INPUT_1") (pintype "bidirectional"))
    )
    (net (code "578") (name "{slash}SO") (class "Default")
      (node (ref "CONN1") (pin "16") (pinfunction "16_16") (pintype "passive"))
      (node (ref "U6B") (pin "16") (pinfunction "PC2_16") (pintype "bidirectional"))
    )
    (net (code "579") (name "{slash}WE") (class "Default")
      (node (ref "U4A") (pin "29") (pinfunction "WE_29") (pintype "input"))
      (node (ref "U4B") (pin "29") (pinfunction "WE_29") (pintype "input"))
      (node (ref "U8A") (pin "57") (pinfunction "MC88_57") (pintype "bidirectional"))
    )
  )
)
